# USBhub.net
KiCad netlist of a schematic drawn in Altium Designer
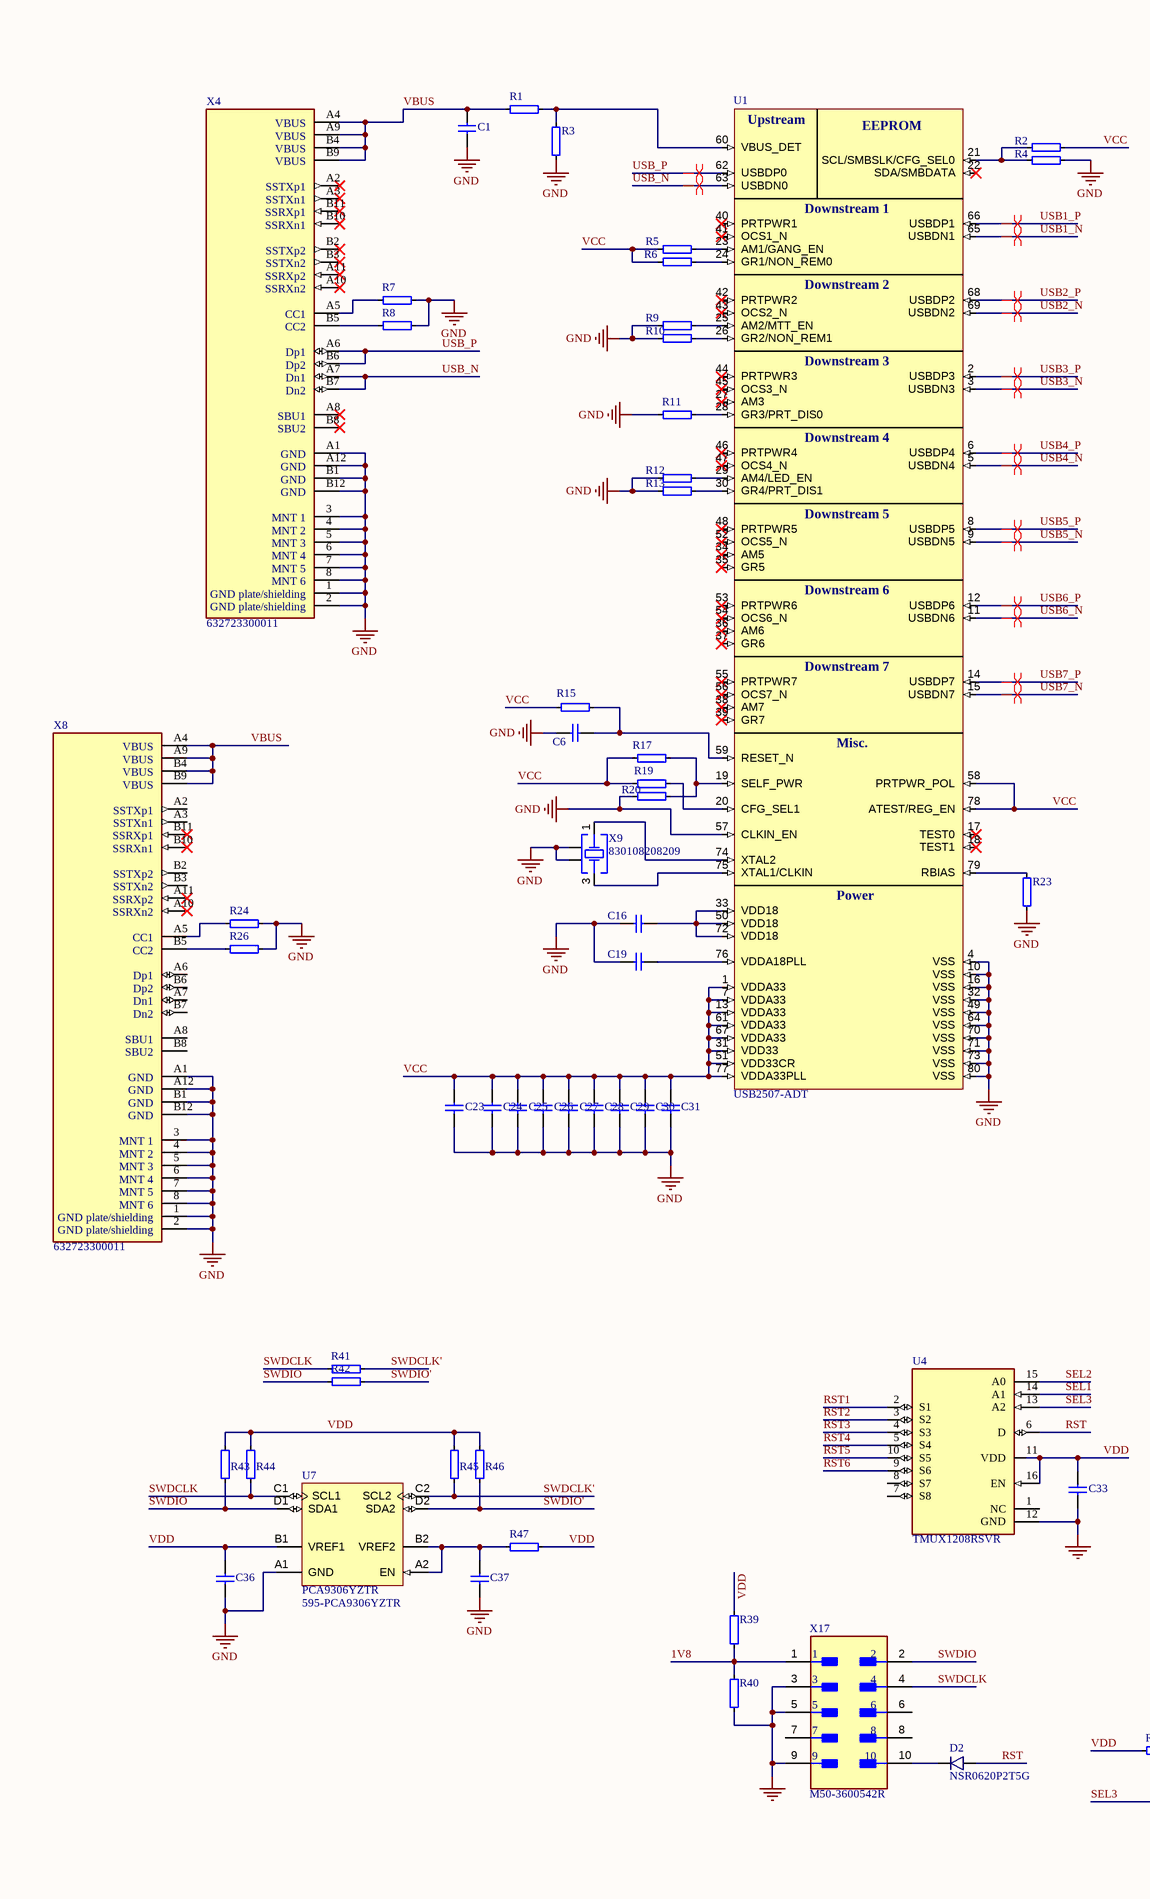
[diagram p0: USBhub.SchDoc, left]
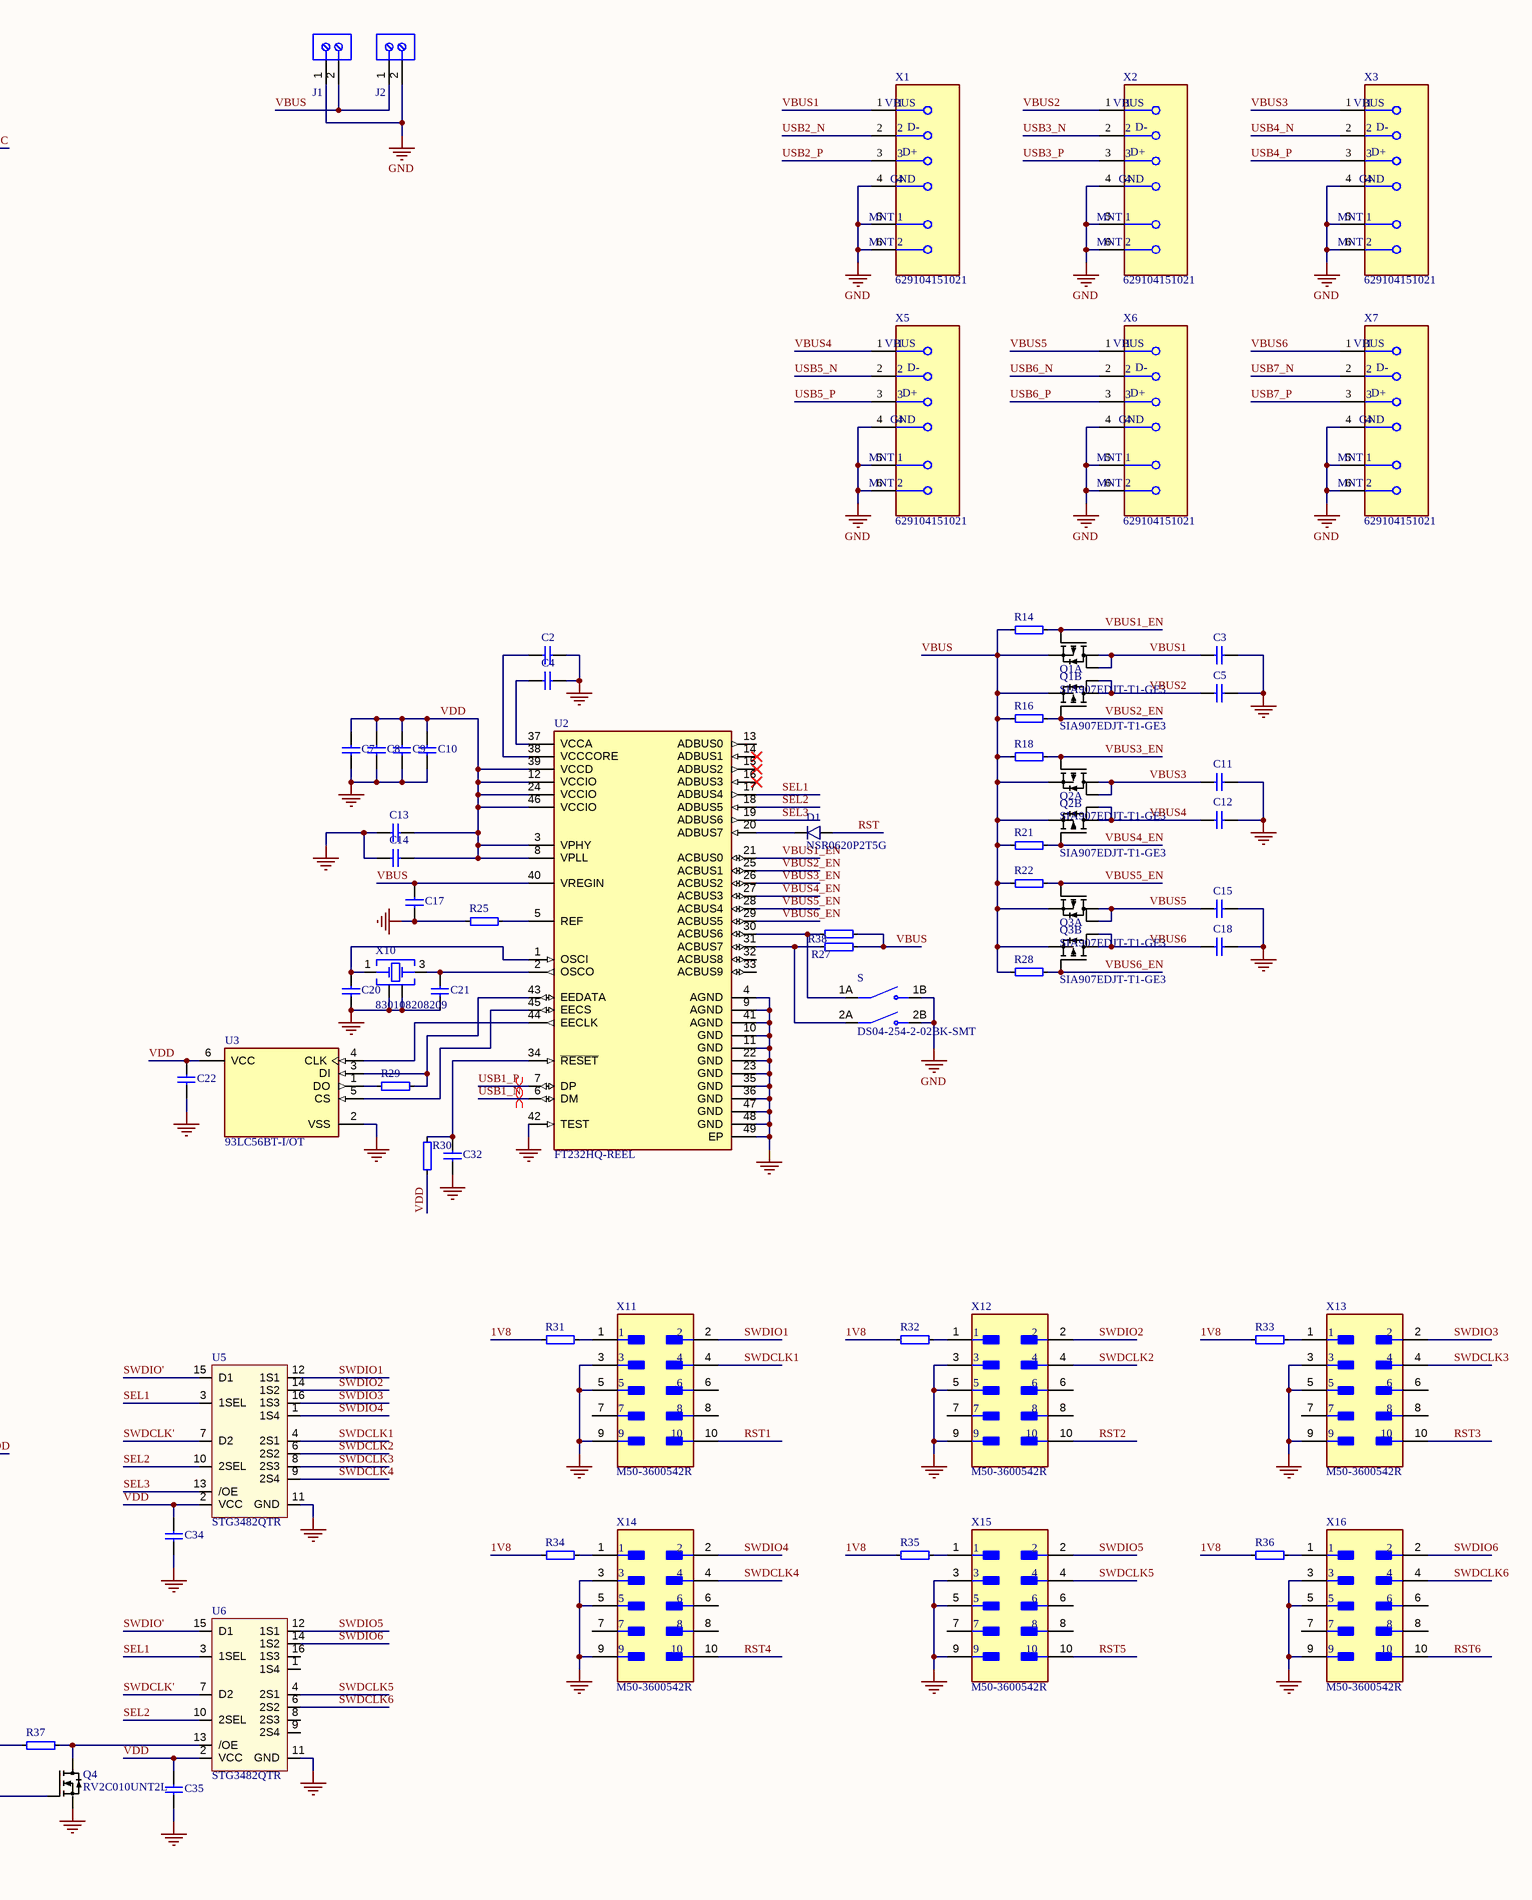
[diagram p1: USBhub.SchDoc, right]

(export (version "E")
  (design (tool "Eeschema 10.0.6"))
  (components
    (comp (ref "C1") (value "C0402") (footprint "CAPC1005X04L") (libsource (lib "Schlib1") (part "C0402")))
    (comp (ref "C2") (value "C0201") (footprint "CAPC0603X03L_C") (libsource (lib "Schlib1") (part "C0201")))
    (comp (ref "C3") (value "C0402") (footprint "CAPC1005X04L") (libsource (lib "Schlib1") (part "C0402")))
    (comp (ref "C4") (value "C0201") (footprint "CAPC0603X03L_C") (libsource (lib "Schlib1") (part "C0201")))
    (comp (ref "C5") (value "C0402") (footprint "CAPC1005X04L") (libsource (lib "Schlib1") (part "C0402")))
    (comp (ref "C6") (value "C0201") (footprint "CAPC0603X03L_C") (libsource (lib "Schlib1") (part "C0201")))
    (comp (ref "C7") (value "C0201") (footprint "CAPC0603X03L_C") (libsource (lib "Schlib1") (part "C0201")))
    (comp (ref "C8") (value "C0201") (footprint "CAPC0603X03L_C") (libsource (lib "Schlib1") (part "C0201")))
    (comp (ref "C9") (value "C0201") (footprint "CAPC0603X03L_C") (libsource (lib "Schlib1") (part "C0201")))
    (comp (ref "C10") (value "C0201") (footprint "CAPC0603X03L_C") (libsource (lib "Schlib1") (part "C0201")))
    (comp (ref "C11") (value "C0402") (footprint "CAPC1005X04L") (libsource (lib "Schlib1") (part "C0402")))
    (comp (ref "C12") (value "C0402") (footprint "CAPC1005X04L") (libsource (lib "Schlib1") (part "C0402")))
    (comp (ref "C13") (value "C0201") (footprint "CAPC0603X03L_C") (libsource (lib "Schlib1") (part "C0201")))
    (comp (ref "C14") (value "C0201") (footprint "CAPC0603X03L_C") (libsource (lib "Schlib1") (part "C0201")))
    (comp (ref "C15") (value "C0402") (footprint "CAPC1005X04L") (libsource (lib "Schlib1") (part "C0402")))
    (comp (ref "C16") (value "C0402") (footprint "CAPC1005X04L") (libsource (lib "Schlib1") (part "C0402")))
    (comp (ref "C17") (value "C0201") (footprint "CAPC0603X03L_C") (libsource (lib "Schlib1") (part "C0201")))
    (comp (ref "C18") (value "C0402") (footprint "CAPC1005X04L") (libsource (lib "Schlib1") (part "C0402")))
    (comp (ref "C19") (value "C0402") (footprint "CAPC1005X04L") (libsource (lib "Schlib1") (part "C0402")))
    (comp (ref "C20") (value "C0201") (footprint "CAPC0603X03L_C") (libsource (lib "Schlib1") (part "C0201")))
    (comp (ref "C21") (value "C0201") (footprint "CAPC0603X03L_C") (libsource (lib "Schlib1") (part "C0201")))
    (comp (ref "C22") (value "C0201") (footprint "CAPC0603X03L_C") (libsource (lib "Schlib1") (part "C0201")))
    (comp (ref "C23") (value "C0603") (footprint "CAPC1608X06L") (libsource (lib "Schlib1") (part "C0603")))
    (comp (ref "C24") (value "C0201") (footprint "CAPC0603X03L_C") (libsource (lib "Schlib1") (part "C0201")))
    (comp (ref "C25") (value "C0201") (footprint "CAPC0603X03L_C") (libsource (lib "Schlib1") (part "C0201")))
    (comp (ref "C26") (value "C0201") (footprint "CAPC0603X03L_C") (libsource (lib "Schlib1") (part "C0201")))
    (comp (ref "C27") (value "C0201") (footprint "CAPC0603X03L_C") (libsource (lib "Schlib1") (part "C0201")))
    (comp (ref "C28") (value "C0201") (footprint "CAPC0603X03L_C") (libsource (lib "Schlib1") (part "C0201")))
    (comp (ref "C29") (value "C0201") (footprint "CAPC0603X03L_C") (libsource (lib "Schlib1") (part "C0201")))
    (comp (ref "C30") (value "C0201") (footprint "CAPC0603X03L_C") (libsource (lib "Schlib1") (part "C0201")))
    (comp (ref "C31") (value "C0201") (footprint "CAPC0603X03L_C") (libsource (lib "Schlib1") (part "C0201")))
    (comp (ref "C32") (value "C0201") (footprint "CAPC0603X03L_C") (libsource (lib "Schlib1") (part "C0201")))
    (comp (ref "C33") (value "C0201") (footprint "CAPC0603X03L_C") (libsource (lib "Schlib1") (part "C0201")))
    (comp (ref "C34") (value "C0201") (footprint "CAPC0603X03L_C") (libsource (lib "Schlib1") (part "C0201")))
    (comp (ref "C35") (value "C0201") (footprint "CAPC0603X03L_C") (libsource (lib "Schlib1") (part "C0201")))
    (comp (ref "C36") (value "C0201") (footprint "CAPC0603X03L_C") (libsource (lib "Schlib1") (part "C0201")))
    (comp (ref "C37") (value "C0201") (footprint "CAPC0603X03L_C") (libsource (lib "Schlib1") (part "C0201")))
    (comp (ref "D1")
      (value "NSR0620P2T5G")
      (footprint "SODFL100X40-2N")
      (description "20V schottky barrier diode, Vf 350 mV @ 100 mA, Ir 2.0 µA @ 10 V, If 500 mA")
      (fields (field (name "MANUFACTURER") "ON Semiconductor"))
      (libsource (lib "Schlib1") (part "NSR0620P2T5G"))
    )
    (comp (ref "D2")
      (value "NSR0620P2T5G")
      (footprint "SODFL100X40-2N")
      (description "20V schottky barrier diode, Vf 350 mV @ 100 mA, Ir 2.0 µA @ 10 V, If 500 mA")
      (fields (field (name "MANUFACTURER") "ON Semiconductor"))
      (libsource (lib "Schlib1") (part "NSR0620P2T5G"))
    )
    (comp (ref "J1")
      (value "691103110002")
      (footprint "691103110002")
      (description "WR-TBL Series 1031 Horizontal Entry Modular, Through Hole, pitch 3.5mm, 2p")
      (fields (field (name "MANUFACTURER") "Wurth Elektronik"))
      (libsource (lib "Schlib1") (part "691103110002"))
    )
    (comp (ref "J2")
      (value "691103110002")
      (footprint "691103110002")
      (description "WR-TBL Series 1031 Horizontal Entry Modular, Through Hole, pitch 3.5mm, 2p")
      (fields (field (name "MANUFACTURER") "Wurth Elektronik"))
      (libsource (lib "Schlib1") (part "691103110002"))
    )
    (comp (ref "Q1")
      (value "SIA907EDJT-T1-GE3")
      (footprint "FP-C-07431-DUAL-MFG")
      (description "SiA907EDJT Series Dual P Channel 20 V 0.057 Ohm 7.8 W Mosfet - PowerPAK SC-70-6L")
      (fields (field (name "MANUFACTURER") "Vishay Siliconix"))
      (libsource (lib "Schlib1") (part "SIA907EDJT-T1-GE3"))
    )
    (comp (ref "Q2")
      (value "SIA907EDJT-T1-GE3")
      (footprint "FP-C-07431-DUAL-MFG")
      (description "SiA907EDJT Series Dual P Channel 20 V 0.057 Ohm 7.8 W Mosfet - PowerPAK SC-70-6L")
      (fields (field (name "MANUFACTURER") "Vishay Siliconix"))
      (libsource (lib "Schlib1") (part "SIA907EDJT-T1-GE3"))
    )
    (comp (ref "Q3")
      (value "SIA907EDJT-T1-GE3")
      (footprint "FP-C-07431-DUAL-MFG")
      (description "SiA907EDJT Series Dual P Channel 20 V 0.057 Ohm 7.8 W Mosfet - PowerPAK SC-70-6L")
      (fields (field (name "MANUFACTURER") "Vishay Siliconix"))
      (libsource (lib "Schlib1") (part "SIA907EDJT-T1-GE3"))
    )
    (comp (ref "Q4")
      (value "RV2C010UNT2L")
      (footprint "DFN65P100X40-3L")
      (description "MOSFET Transistor, N Channel, 1 A, 20 V, 0.34 ohm, 4.5 V, 1 V RoHS Compliant: Yes")
      (fields (field (name "MANUFACTURER") "Rohm"))
      (libsource (lib "Schlib1") (part "RV2C010UNT2L"))
    )
    (comp (ref "R1") (value "R0201") (footprint "RESC0603X03L_C") (libsource (lib "Schlib1") (part "R0201")))
    (comp (ref "R2") (value "R0201") (footprint "RESC0603X03L_C") (libsource (lib "Schlib1") (part "R0201")))
    (comp (ref "R3") (value "R0201") (footprint "RESC0603X03L_C") (libsource (lib "Schlib1") (part "R0201")))
    (comp (ref "R4") (value "R0201") (footprint "RESC0603X03L_C") (libsource (lib "Schlib1") (part "R0201")))
    (comp (ref "R5") (value "R0201") (footprint "RESC0603X03L_C") (libsource (lib "Schlib1") (part "R0201")))
    (comp (ref "R6") (value "R0201") (footprint "RESC0603X03L_C") (libsource (lib "Schlib1") (part "R0201")))
    (comp (ref "R7") (value "R0201") (footprint "RESC0603X03L_C") (libsource (lib "Schlib1") (part "R0201")))
    (comp (ref "R8") (value "R0201") (footprint "RESC0603X03L_C") (libsource (lib "Schlib1") (part "R0201")))
    (comp (ref "R9") (value "R0201") (footprint "RESC0603X03L_C") (libsource (lib "Schlib1") (part "R0201")))
    (comp (ref "R10") (value "R0201") (footprint "RESC0603X03L_C") (libsource (lib "Schlib1") (part "R0201")))
    (comp (ref "R11") (value "R0201") (footprint "RESC0603X03L_C") (libsource (lib "Schlib1") (part "R0201")))
    (comp (ref "R12") (value "R0201") (footprint "RESC0603X03L_C") (libsource (lib "Schlib1") (part "R0201")))
    (comp (ref "R13") (value "R0201") (footprint "RESC0603X03L_C") (libsource (lib "Schlib1") (part "R0201")))
    (comp (ref "R14") (value "R0201") (footprint "RESC0603X03L_C") (libsource (lib "Schlib1") (part "R0201")))
    (comp (ref "R15") (value "R0201") (footprint "RESC0603X03L_C") (libsource (lib "Schlib1") (part "R0201")))
    (comp (ref "R16") (value "R0201") (footprint "RESC0603X03L_C") (libsource (lib "Schlib1") (part "R0201")))
    (comp (ref "R17") (value "R0201") (footprint "RESC0603X03L_C") (libsource (lib "Schlib1") (part "R0201")))
    (comp (ref "R18") (value "R0201") (footprint "RESC0603X03L_C") (libsource (lib "Schlib1") (part "R0201")))
    (comp (ref "R19") (value "R0201") (footprint "RESC0603X03L_C") (libsource (lib "Schlib1") (part "R0201")))
    (comp (ref "R20") (value "R0201") (footprint "RESC0603X03L_C") (libsource (lib "Schlib1") (part "R0201")))
    (comp (ref "R21") (value "R0201") (footprint "RESC0603X03L_C") (libsource (lib "Schlib1") (part "R0201")))
    (comp (ref "R22") (value "R0201") (footprint "RESC0603X03L_C") (libsource (lib "Schlib1") (part "R0201")))
    (comp (ref "R23") (value "R0201") (footprint "RESC0603X03L_C") (libsource (lib "Schlib1") (part "R0201")))
    (comp (ref "R24") (value "R0201") (footprint "RESC0603X03L_C") (libsource (lib "Schlib1") (part "R0201")))
    (comp (ref "R25") (value "R0201") (footprint "RESC0603X03L_C") (libsource (lib "Schlib1") (part "R0201")))
    (comp (ref "R26") (value "R0201") (footprint "RESC0603X03L_C") (libsource (lib "Schlib1") (part "R0201")))
    (comp (ref "R27") (value "R0201") (footprint "RESC0603X03L_C") (libsource (lib "Schlib1") (part "R0201")))
    (comp (ref "R28") (value "R0201") (footprint "RESC0603X03L_C") (libsource (lib "Schlib1") (part "R0201")))
    (comp (ref "R29") (value "R0201") (footprint "RESC0603X03L_C") (libsource (lib "Schlib1") (part "R0201")))
    (comp (ref "R30") (value "R0201") (footprint "RESC0603X03L_C") (libsource (lib "Schlib1") (part "R0201")))
    (comp (ref "R31") (value "R0201") (footprint "RESC0603X03L_C") (libsource (lib "Schlib1") (part "R0201")))
    (comp (ref "R32") (value "R0201") (footprint "RESC0603X03L_C") (libsource (lib "Schlib1") (part "R0201")))
    (comp (ref "R33") (value "R0201") (footprint "RESC0603X03L_C") (libsource (lib "Schlib1") (part "R0201")))
    (comp (ref "R34") (value "R0201") (footprint "RESC0603X03L_C") (libsource (lib "Schlib1") (part "R0201")))
    (comp (ref "R35") (value "R0201") (footprint "RESC0603X03L_C") (libsource (lib "Schlib1") (part "R0201")))
    (comp (ref "R36") (value "R0201") (footprint "RESC0603X03L_C") (libsource (lib "Schlib1") (part "R0201")))
    (comp (ref "R37") (value "R0201") (footprint "RESC0603X03L_C") (libsource (lib "Schlib1") (part "R0201")))
    (comp (ref "R38") (value "R0201") (footprint "RESC0603X03L_C") (libsource (lib "Schlib1") (part "R0201")))
    (comp (ref "R39") (value "R0201") (footprint "RESC0603X03L_C") (libsource (lib "Schlib1") (part "R0201")))
    (comp (ref "R40") (value "R0201") (footprint "RESC0603X03L_C") (libsource (lib "Schlib1") (part "R0201")))
    (comp (ref "R41") (value "R0201") (footprint "RESC0603X03L_C") (libsource (lib "Schlib1") (part "R0201")))
    (comp (ref "R42") (value "R0201") (footprint "RESC0603X03L_C") (libsource (lib "Schlib1") (part "R0201")))
    (comp (ref "R43") (value "R0201") (footprint "RESC0603X03L_C") (libsource (lib "Schlib1") (part "R0201")))
    (comp (ref "R44") (value "R0201") (footprint "RESC0603X03L_C") (libsource (lib "Schlib1") (part "R0201")))
    (comp (ref "R45") (value "R0201") (footprint "RESC0603X03L_C") (libsource (lib "Schlib1") (part "R0201")))
    (comp (ref "R46") (value "R0201") (footprint "RESC0603X03L_C") (libsource (lib "Schlib1") (part "R0201")))
    (comp (ref "R47") (value "R0201") (footprint "RESC0603X03L_C") (libsource (lib "Schlib1") (part "R0201")))
    (comp (ref "S")
      (value "DS04-254-2-02BK-SMT")
      (footprint "PcbLib1:SW_DS04-254-2-02BK-SMT")
      (description "2 Pole, Flat Actuator, Flat Bottom, SMT Pin, DIP Switch")
      (fields (field (name "MF") "CUI Devices"))
      (libsource (lib "Schlib1") (part "DS04-254-2-02BK-SMT"))
    )
    (comp (ref "U1")
      (value "USB2507-ADT")
      (footprint "USB2507-ADT")
      (description "Low Speed/Full Speed/High Speed Compatible 7 Port Hub USB 2.0 1.8V/3.3V Tray 80-Pin TQFP")
      (fields (field (name "MANUFACTURER") "Microchip"))
      (libsource (lib "Schlib1") (part "USB2507-ADT"))
    )
    (comp (ref "U2")
      (value "FT232HQ-REEL")
      (footprint "FT232HQ")
      (description "Full Speed/High Speed USB Interface Device USB 2.0 3.3V T/R 48-Pin QFN EP")
      (fields (field (name "MANUFACTURER") "FTDI"))
      (libsource (lib "Schlib1") (part "FT232HQ-REEL"))
    )
    (comp (ref "U3")
      (value "93LC56BT-I/OT")
      (footprint "93LC56BT-I/OT_sot23-6")
      (description "RES 1 OHM 1/2W 5% AXIAL")
      (fields (field (name "MANUFACTURER") "Microchip"))
      (libsource (lib "Schlib1") (part "93LC56BT-I/OT"))
    )
    (comp (ref "U4")
      (value "TMUX1208RSVR")
      (footprint "FP-RSV0016A-MFG")
      (description "5-V, 8: 1, 1-channel general-purpose analog multiplexer with 1.8-V input logic 16-UQFN -40 to 125")
      (fields (field (name "MANUFACTURER") "Texas Instruments"))
      (libsource (lib "Schlib1") (part "TMUX1208RSVR"))
    )
    (comp (ref "U5")
      (value "STG3482QTR")
      (footprint "STG3482QTR")
      (description "Low Voltage Dual SP4T Switch with Break-Before-Make Feat.")
      (fields (field (name "MANUFACTURER") "STMicroelectronics"))
      (libsource (lib "Schlib1") (part "STG3482QTR"))
    )
    (comp (ref "U6")
      (value "STG3482QTR")
      (footprint "STG3482QTR")
      (description "Low Voltage Dual SP4T Switch with Break-Before-Make Feat.")
      (fields (field (name "MANUFACTURER") "STMicroelectronics"))
      (libsource (lib "Schlib1") (part "STG3482QTR"))
    )
    (comp (ref "U7")
      (value "PCA9306YZTR")
      (footprint "PCA9306YZTR")
      (description "PCA9306 2-BIT Bidirectional I2C")
      (fields
        (field (name "MANUFACTURER") "Texas Instruments")
        (field (name "SUPPLIER PART NUMBER 1") "595-PCA9306YZTR")
      )
      (libsource (lib "Schlib1") (part "PCA9306YZTR"))
    )
    (comp (ref "X1")
      (value "629104151021")
      (footprint "FP-629104151021-MFG")
      (description "USB 2.0 Type A Receptacle WR-COM, Horizontal, SMT, with Pegs")
      (fields (field (name "MANUFACTURER") "Wurth Electronics"))
      (libsource (lib "Schlib1") (part "629104151021"))
    )
    (comp (ref "X2")
      (value "629104151021")
      (footprint "FP-629104151021-MFG")
      (description "USB 2.0 Type A Receptacle WR-COM, Horizontal, SMT, with Pegs")
      (fields (field (name "MANUFACTURER") "Wurth Electronics"))
      (libsource (lib "Schlib1") (part "629104151021"))
    )
    (comp (ref "X3")
      (value "629104151021")
      (footprint "FP-629104151021-MFG")
      (description "USB 2.0 Type A Receptacle WR-COM, Horizontal, SMT, with Pegs")
      (fields (field (name "MANUFACTURER") "Wurth Electronics"))
      (libsource (lib "Schlib1") (part "629104151021"))
    )
    (comp (ref "X4")
      (value "632723300011")
      (footprint "FP-632723300011-MFG")
      (description "Conn USB 3.1 Type C RCP 24 POS 0.5mm/0.4mm Solder RA SMD/Thru-Hole 24 Terminal 1 Port T/R")
      (fields (field (name "MANUFACTURER") "Wurth Electronics"))
      (libsource (lib "Schlib1") (part "632723300011"))
    )
    (comp (ref "X5")
      (value "629104151021")
      (footprint "FP-629104151021-MFG")
      (description "USB 2.0 Type A Receptacle WR-COM, Horizontal, SMT, with Pegs")
      (fields (field (name "MANUFACTURER") "Wurth Electronics"))
      (libsource (lib "Schlib1") (part "629104151021"))
    )
    (comp (ref "X6")
      (value "629104151021")
      (footprint "FP-629104151021-MFG")
      (description "USB 2.0 Type A Receptacle WR-COM, Horizontal, SMT, with Pegs")
      (fields (field (name "MANUFACTURER") "Wurth Electronics"))
      (libsource (lib "Schlib1") (part "629104151021"))
    )
    (comp (ref "X7")
      (value "629104151021")
      (footprint "FP-629104151021-MFG")
      (description "USB 2.0 Type A Receptacle WR-COM, Horizontal, SMT, with Pegs")
      (fields (field (name "MANUFACTURER") "Wurth Electronics"))
      (libsource (lib "Schlib1") (part "629104151021"))
    )
    (comp (ref "X8")
      (value "632723300011")
      (footprint "FP-632723300011-MFG")
      (description "Conn USB 3.1 Type C RCP 24 POS 0.5mm/0.4mm Solder RA SMD/Thru-Hole 24 Terminal 1 Port T/R")
      (fields (field (name "MANUFACTURER") "Wurth Electronics"))
      (libsource (lib "Schlib1") (part "632723300011"))
    )
    (comp (ref "X9")
      (value "830108208209")
      (footprint "WE-XTAL_CFPX-218")
      (fields (field (name "MANUFACTURER") "Wurth Electronics"))
      (libsource (lib "Schlib1") (part "830108208209"))
    )
    (comp (ref "X10")
      (value "830108208209")
      (footprint "WE-XTAL_CFPX-218")
      (fields (field (name "MANUFACTURER") "Wurth Electronics"))
      (libsource (lib "Schlib1") (part "830108208209"))
    )
    (comp (ref "X11")
      (value "M50-3600542R")
      (footprint "M50-3600542R")
      (description "Conn Unshrouded Header M 10 POS 1.27mm Solder ST Top Entry SMD T/R")
      (fields (field (name "MANUFACTURER") "Harwin"))
      (libsource (lib "Schlib1") (part "M50-3600542R"))
    )
    (comp (ref "X12")
      (value "M50-3600542R")
      (footprint "M50-3600542R")
      (description "Conn Unshrouded Header M 10 POS 1.27mm Solder ST Top Entry SMD T/R")
      (fields (field (name "MANUFACTURER") "Harwin"))
      (libsource (lib "Schlib1") (part "M50-3600542R"))
    )
    (comp (ref "X13")
      (value "M50-3600542R")
      (footprint "M50-3600542R")
      (description "Conn Unshrouded Header M 10 POS 1.27mm Solder ST Top Entry SMD T/R")
      (fields (field (name "MANUFACTURER") "Harwin"))
      (libsource (lib "Schlib1") (part "M50-3600542R"))
    )
    (comp (ref "X14")
      (value "M50-3600542R")
      (footprint "M50-3600542R")
      (description "Conn Unshrouded Header M 10 POS 1.27mm Solder ST Top Entry SMD T/R")
      (fields (field (name "MANUFACTURER") "Harwin"))
      (libsource (lib "Schlib1") (part "M50-3600542R"))
    )
    (comp (ref "X15")
      (value "M50-3600542R")
      (footprint "M50-3600542R")
      (description "Conn Unshrouded Header M 10 POS 1.27mm Solder ST Top Entry SMD T/R")
      (fields (field (name "MANUFACTURER") "Harwin"))
      (libsource (lib "Schlib1") (part "M50-3600542R"))
    )
    (comp (ref "X16")
      (value "M50-3600542R")
      (footprint "M50-3600542R")
      (description "Conn Unshrouded Header M 10 POS 1.27mm Solder ST Top Entry SMD T/R")
      (fields (field (name "MANUFACTURER") "Harwin"))
      (libsource (lib "Schlib1") (part "M50-3600542R"))
    )
    (comp (ref "X17")
      (value "M50-3600542R")
      (footprint "M50-3600542R")
      (description "Conn Unshrouded Header M 10 POS 1.27mm Solder ST Top Entry SMD T/R")
      (fields (field (name "MANUFACTURER") "Harwin"))
      (libsource (lib "Schlib1") (part "M50-3600542R"))
    )
  )
  (nets
    (net (code "1") (name "/1V8") (class "Default")
      (node (ref "R31") (pin "2") (pinfunction "2_2") (pintype "passive"))
      (node (ref "R32") (pin "2") (pinfunction "2_2") (pintype "passive"))
      (node (ref "R33") (pin "2") (pinfunction "2_2") (pintype "passive"))
      (node (ref "R34") (pin "2") (pinfunction "2_2") (pintype "passive"))
      (node (ref "R35") (pin "2") (pinfunction "2_2") (pintype "passive"))
      (node (ref "R36") (pin "2") (pinfunction "2_2") (pintype "passive"))
      (node (ref "R39") (pin "2") (pinfunction "2_2") (pintype "passive"))
      (node (ref "R40") (pin "1") (pinfunction "1_1") (pintype "passive"))
      (node (ref "X17") (pin "1") (pinfunction "1_1") (pintype "passive"))
    )
    (net (code "2") (name "/RST") (class "Default")
      (node (ref "D1") (pin "2") (pinfunction "A_2") (pintype "passive"))
      (node (ref "D2") (pin "2") (pinfunction "A_2") (pintype "passive"))
      (node (ref "U4") (pin "6") (pinfunction "D_6") (pintype "bidirectional"))
    )
    (net (code "3") (name "/RST1") (class "Default")
      (node (ref "U4") (pin "2") (pinfunction "S1_2") (pintype "bidirectional"))
      (node (ref "X11") (pin "10") (pinfunction "10_10") (pintype "passive"))
    )
    (net (code "4") (name "/RST2") (class "Default")
      (node (ref "U4") (pin "3") (pinfunction "S2_3") (pintype "bidirectional"))
      (node (ref "X12") (pin "10") (pinfunction "10_10") (pintype "passive"))
    )
    (net (code "5") (name "/RST3") (class "Default")
      (node (ref "U4") (pin "4") (pinfunction "S3_4") (pintype "bidirectional"))
      (node (ref "X13") (pin "10") (pinfunction "10_10") (pintype "passive"))
    )
    (net (code "6") (name "/RST4") (class "Default")
      (node (ref "U4") (pin "5") (pinfunction "S4_5") (pintype "bidirectional"))
      (node (ref "X14") (pin "10") (pinfunction "10_10") (pintype "passive"))
    )
    (net (code "7") (name "/RST5") (class "Default")
      (node (ref "U4") (pin "10") (pinfunction "S5_10") (pintype "bidirectional"))
      (node (ref "X15") (pin "10") (pinfunction "10_10") (pintype "passive"))
    )
    (net (code "8") (name "/RST6") (class "Default")
      (node (ref "U4") (pin "9") (pinfunction "S6_9") (pintype "bidirectional"))
      (node (ref "X16") (pin "10") (pinfunction "10_10") (pintype "passive"))
    )
    (net (code "9") (name "/SEL1") (class "Default")
      (node (ref "U2") (pin "17") (pinfunction "ADBUS4_17") (pintype "output"))
      (node (ref "U4") (pin "14") (pinfunction "A1_14") (pintype "input"))
      (node (ref "U5") (pin "3") (pinfunction "1SEL_3") (pintype "passive"))
      (node (ref "U6") (pin "3") (pinfunction "1SEL_3") (pintype "passive"))
    )
    (net (code "10") (name "/SEL2") (class "Default")
      (node (ref "U2") (pin "18") (pinfunction "ADBUS5_18") (pintype "input"))
      (node (ref "U4") (pin "15") (pinfunction "A0_15") (pintype "passive"))
      (node (ref "U5") (pin "10") (pinfunction "2SEL_10") (pintype "passive"))
      (node (ref "U6") (pin "10") (pinfunction "2SEL_10") (pintype "passive"))
    )
    (net (code "11") (name "/SEL3") (class "Default")
      (node (ref "Q4") (pin "1") (pinfunction "G_1") (pintype "passive"))
      (node (ref "U2") (pin "19") (pinfunction "ADBUS6_19") (pintype "output"))
      (node (ref "U4") (pin "13") (pinfunction "A2_13") (pintype "input"))
      (node (ref "U5") (pin "13") (pinfunction "/OE_13") (pintype "passive"))
    )
    (net (code "12") (name "/SWDCLK") (class "Default")
      (node (ref "R41") (pin "2") (pinfunction "2_2") (pintype "passive"))
      (node (ref "R44") (pin "1") (pinfunction "1_1") (pintype "passive"))
      (node (ref "U7") (pin "C1") (pinfunction "SCL1_C1") (pintype "bidirectional"))
      (node (ref "X17") (pin "4") (pinfunction "4_4") (pintype "passive"))
    )
    (net (code "13") (name "/SWDCLK'") (class "Default")
      (node (ref "R41") (pin "1") (pinfunction "1_1") (pintype "passive"))
      (node (ref "R45") (pin "1") (pinfunction "1_1") (pintype "passive"))
      (node (ref "U5") (pin "7") (pinfunction "D2_7") (pintype "passive"))
      (node (ref "U6") (pin "7") (pinfunction "D2_7") (pintype "passive"))
      (node (ref "U7") (pin "C2") (pinfunction "SCL2_C2") (pintype "bidirectional"))
    )
    (net (code "14") (name "/SWDCLK1") (class "Default")
      (node (ref "U5") (pin "4") (pinfunction "2S1_4") (pintype "passive"))
      (node (ref "X11") (pin "4") (pinfunction "4_4") (pintype "passive"))
    )
    (net (code "15") (name "/SWDCLK2") (class "Default")
      (node (ref "U5") (pin "6") (pinfunction "2S2_6") (pintype "passive"))
      (node (ref "X12") (pin "4") (pinfunction "4_4") (pintype "passive"))
    )
    (net (code "16") (name "/SWDCLK3") (class "Default")
      (node (ref "U5") (pin "8") (pinfunction "2S3_8") (pintype "passive"))
      (node (ref "X13") (pin "4") (pinfunction "4_4") (pintype "passive"))
    )
    (net (code "17") (name "/SWDCLK4") (class "Default")
      (node (ref "U5") (pin "9") (pinfunction "2S4_9") (pintype "passive"))
      (node (ref "X14") (pin "4") (pinfunction "4_4") (pintype "passive"))
    )
    (net (code "18") (name "/SWDCLK5") (class "Default")
      (node (ref "U6") (pin "4") (pinfunction "2S1_4") (pintype "passive"))
      (node (ref "X15") (pin "4") (pinfunction "4_4") (pintype "passive"))
    )
    (net (code "19") (name "/SWDCLK6") (class "Default")
      (node (ref "U6") (pin "6") (pinfunction "2S2_6") (pintype "passive"))
      (node (ref "X16") (pin "4") (pinfunction "4_4") (pintype "passive"))
    )
    (net (code "20") (name "/SWDIO") (class "Default")
      (node (ref "R42") (pin "2") (pinfunction "2_2") (pintype "passive"))
      (node (ref "R43") (pin "1") (pinfunction "1_1") (pintype "passive"))
      (node (ref "U7") (pin "D1") (pinfunction "SDA1_D1") (pintype "bidirectional"))
      (node (ref "X17") (pin "2") (pinfunction "2_2") (pintype "passive"))
    )
    (net (code "21") (name "/SWDIO'") (class "Default")
      (node (ref "R42") (pin "1") (pinfunction "1_1") (pintype "passive"))
      (node (ref "R46") (pin "1") (pinfunction "1_1") (pintype "passive"))
      (node (ref "U5") (pin "15") (pinfunction "D1_15") (pintype "passive"))
      (node (ref "U6") (pin "15") (pinfunction "D1_15") (pintype "passive"))
      (node (ref "U7") (pin "D2") (pinfunction "SDA2_D2") (pintype "bidirectional"))
    )
    (net (code "22") (name "/SWDIO1") (class "Default")
      (node (ref "U5") (pin "12") (pinfunction "1S1_12") (pintype "passive"))
      (node (ref "X11") (pin "2") (pinfunction "2_2") (pintype "passive"))
    )
    (net (code "23") (name "/SWDIO2") (class "Default")
      (node (ref "U5") (pin "14") (pinfunction "1S2_14") (pintype "passive"))
      (node (ref "X12") (pin "2") (pinfunction "2_2") (pintype "passive"))
    )
    (net (code "24") (name "/SWDIO3") (class "Default")
      (node (ref "U5") (pin "16") (pinfunction "1S3_16") (pintype "passive"))
      (node (ref "X13") (pin "2") (pinfunction "2_2") (pintype "passive"))
    )
    (net (code "25") (name "/SWDIO4") (class "Default")
      (node (ref "U5") (pin "1") (pinfunction "1S4_1") (pintype "passive"))
      (node (ref "X14") (pin "2") (pinfunction "2_2") (pintype "passive"))
    )
    (net (code "26") (name "/SWDIO5") (class "Default")
      (node (ref "U6") (pin "12") (pinfunction "1S1_12") (pintype "passive"))
      (node (ref "X15") (pin "2") (pinfunction "2_2") (pintype "passive"))
    )
    (net (code "27") (name "/SWDIO6") (class "Default")
      (node (ref "U6") (pin "14") (pinfunction "1S2_14") (pintype "passive"))
      (node (ref "X16") (pin "2") (pinfunction "2_2") (pintype "passive"))
    )
    (net (code "28") (name "/USB1_N") (class "Default")
      (node (ref "U1") (pin "65") (pinfunction "USBDN1_65") (pintype "input"))
      (node (ref "U2") (pin "6") (pinfunction "DM_6") (pintype "bidirectional"))
    )
    (net (code "29") (name "/USB1_P") (class "Default")
      (node (ref "U1") (pin "66") (pinfunction "USBDP1_66") (pintype "input"))
      (node (ref "U2") (pin "7") (pinfunction "DP_7") (pintype "bidirectional"))
    )
    (net (code "30") (name "/USB2_N") (class "Default")
      (node (ref "U1") (pin "69") (pinfunction "USBDN2_69") (pintype "input"))
      (node (ref "X1") (pin "2") (pinfunction "2_2") (pintype "passive"))
    )
    (net (code "31") (name "/USB2_P") (class "Default")
      (node (ref "U1") (pin "68") (pinfunction "USBDP2_68") (pintype "input"))
      (node (ref "X1") (pin "3") (pinfunction "3_3") (pintype "passive"))
    )
    (net (code "32") (name "/USB3_N") (class "Default")
      (node (ref "U1") (pin "3") (pinfunction "USBDN3_3") (pintype "input"))
      (node (ref "X2") (pin "2") (pinfunction "2_2") (pintype "passive"))
    )
    (net (code "33") (name "/USB3_P") (class "Default")
      (node (ref "U1") (pin "2") (pinfunction "USBDP3_2") (pintype "input"))
      (node (ref "X2") (pin "3") (pinfunction "3_3") (pintype "passive"))
    )
    (net (code "34") (name "/USB4_N") (class "Default")
      (node (ref "U1") (pin "5") (pinfunction "USBDN4_5") (pintype "input"))
      (node (ref "X3") (pin "2") (pinfunction "2_2") (pintype "passive"))
    )
    (net (code "35") (name "/USB4_P") (class "Default")
      (node (ref "U1") (pin "6") (pinfunction "USBDP4_6") (pintype "input"))
      (node (ref "X3") (pin "3") (pinfunction "3_3") (pintype "passive"))
    )
    (net (code "36") (name "/USB5_N") (class "Default")
      (node (ref "U1") (pin "9") (pinfunction "USBDN5_9") (pintype "input"))
      (node (ref "X5") (pin "2") (pinfunction "2_2") (pintype "passive"))
    )
    (net (code "37") (name "/USB5_P") (class "Default")
      (node (ref "U1") (pin "8") (pinfunction "USBDP5_8") (pintype "input"))
      (node (ref "X5") (pin "3") (pinfunction "3_3") (pintype "passive"))
    )
    (net (code "38") (name "/USB6_N") (class "Default")
      (node (ref "U1") (pin "11") (pinfunction "USBDN6_11") (pintype "input"))
      (node (ref "X6") (pin "2") (pinfunction "2_2") (pintype "passive"))
    )
    (net (code "39") (name "/USB6_P") (class "Default")
      (node (ref "U1") (pin "12") (pinfunction "USBDP6_12") (pintype "input"))
      (node (ref "X6") (pin "3") (pinfunction "3_3") (pintype "passive"))
    )
    (net (code "40") (name "/USB7_N") (class "Default")
      (node (ref "U1") (pin "15") (pinfunction "USBDN7_15") (pintype "input"))
      (node (ref "X7") (pin "2") (pinfunction "2_2") (pintype "passive"))
    )
    (net (code "41") (name "/USB7_P") (class "Default")
      (node (ref "U1") (pin "14") (pinfunction "USBDP7_14") (pintype "input"))
      (node (ref "X7") (pin "3") (pinfunction "3_3") (pintype "passive"))
    )
    (net (code "42") (name "/USB_N") (class "Default")
      (node (ref "U1") (pin "63") (pinfunction "USBDN0_63") (pintype "input"))
      (node (ref "X4") (pin "A7") (pinfunction "Dn1_A7") (pintype "bidirectional"))
      (node (ref "X4") (pin "B7") (pinfunction "Dn2_B7") (pintype "bidirectional"))
    )
    (net (code "43") (name "/USB_P") (class "Default")
      (node (ref "U1") (pin "62") (pinfunction "USBDP0_62") (pintype "input"))
      (node (ref "X4") (pin "A6") (pinfunction "Dp1_A6") (pintype "bidirectional"))
      (node (ref "X4") (pin "B6") (pinfunction "Dp2_B6") (pintype "bidirectional"))
    )
    (net (code "44") (name "/VBUS") (class "Default")
      (node (ref "C1") (pin "2") (pinfunction "2_2") (pintype "passive"))
      (node (ref "C17") (pin "2") (pinfunction "2_2") (pintype "passive"))
      (node (ref "J1") (pin "2") (pinfunction "2_2") (pintype "passive"))
      (node (ref "J2") (pin "1") (pinfunction "1_1") (pintype "passive"))
      (node (ref "Q1") (pin "1") (pinfunction "S1_1") (pintype "passive"))
      (node (ref "Q1") (pin "4") (pinfunction "S2_4") (pintype "passive"))
      (node (ref "Q2") (pin "1") (pinfunction "S1_1") (pintype "passive"))
      (node (ref "Q2") (pin "4") (pinfunction "S2_4") (pintype "passive"))
      (node (ref "Q3") (pin "1") (pinfunction "S1_1") (pintype "passive"))
      (node (ref "Q3") (pin "4") (pinfunction "S2_4") (pintype "passive"))
      (node (ref "R1") (pin "2") (pinfunction "2_2") (pintype "passive"))
      (node (ref "R14") (pin "2") (pinfunction "2_2") (pintype "passive"))
      (node (ref "R16") (pin "2") (pinfunction "2_2") (pintype "passive"))
      (node (ref "R18") (pin "2") (pinfunction "2_2") (pintype "passive"))
      (node (ref "R21") (pin "2") (pinfunction "2_2") (pintype "passive"))
      (node (ref "R22") (pin "2") (pinfunction "2_2") (pintype "passive"))
      (node (ref "R27") (pin "2") (pinfunction "2_2") (pintype "passive"))
      (node (ref "R28") (pin "2") (pinfunction "2_2") (pintype "passive"))
      (node (ref "R38") (pin "2") (pinfunction "2_2") (pintype "passive"))
      (node (ref "U2") (pin "40") (pinfunction "VREGIN_40") (pintype "power_in"))
      (node (ref "X4") (pin "A4") (pinfunction "VBUS_A4") (pintype "power_in"))
      (node (ref "X4") (pin "A9") (pinfunction "VBUS_A9") (pintype "power_in"))
      (node (ref "X4") (pin "B4") (pinfunction "VBUS_B4") (pintype "power_in"))
      (node (ref "X4") (pin "B9") (pinfunction "VBUS_B9") (pintype "power_in"))
      (node (ref "X8") (pin "A4") (pinfunction "VBUS_A4") (pintype "power_in"))
      (node (ref "X8") (pin "A9") (pinfunction "VBUS_A9") (pintype "power_in"))
      (node (ref "X8") (pin "B4") (pinfunction "VBUS_B4") (pintype "power_in"))
      (node (ref "X8") (pin "B9") (pinfunction "VBUS_B9") (pintype "power_in"))
    )
    (net (code "45") (name "/VBUS1") (class "Default")
      (node (ref "C3") (pin "2") (pinfunction "2_2") (pintype "passive"))
      (node (ref "Q1") (pin "3") (pinfunction "D2_3") (pintype "passive"))
      (node (ref "Q1") (pin "8") (pinfunction "D2_8") (pintype "passive"))
      (node (ref "X1") (pin "1") (pinfunction "1_1") (pintype "passive"))
    )
    (net (code "46") (name "/VBUS1_EN") (class "Default")
      (node (ref "Q1") (pin "5") (pinfunction "G2_5") (pintype "passive"))
      (node (ref "R14") (pin "1") (pinfunction "1_1") (pintype "passive"))
      (node (ref "U2") (pin "21") (pinfunction "ACBUS0_21") (pintype "bidirectional"))
    )
    (net (code "47") (name "/VBUS2") (class "Default")
      (node (ref "C5") (pin "2") (pinfunction "2_2") (pintype "passive"))
      (node (ref "Q1") (pin "6") (pinfunction "D1_6") (pintype "passive"))
      (node (ref "Q1") (pin "7") (pinfunction "D1_7") (pintype "passive"))
      (node (ref "X2") (pin "1") (pinfunction "1_1") (pintype "passive"))
    )
    (net (code "48") (name "/VBUS2_EN") (class "Default")
      (node (ref "Q1") (pin "2") (pinfunction "G1_2") (pintype "passive"))
      (node (ref "R16") (pin "1") (pinfunction "1_1") (pintype "passive"))
      (node (ref "U2") (pin "25") (pinfunction "ACBUS1_25") (pintype "bidirectional"))
    )
    (net (code "49") (name "/VBUS3") (class "Default")
      (node (ref "C11") (pin "2") (pinfunction "2_2") (pintype "passive"))
      (node (ref "Q2") (pin "3") (pinfunction "D2_3") (pintype "passive"))
      (node (ref "Q2") (pin "8") (pinfunction "D2_8") (pintype "passive"))
      (node (ref "X3") (pin "1") (pinfunction "1_1") (pintype "passive"))
    )
    (net (code "50") (name "/VBUS3_EN") (class "Default")
      (node (ref "Q2") (pin "5") (pinfunction "G2_5") (pintype "passive"))
      (node (ref "R18") (pin "1") (pinfunction "1_1") (pintype "passive"))
      (node (ref "U2") (pin "26") (pinfunction "ACBUS2_26") (pintype "bidirectional"))
    )
    (net (code "51") (name "/VBUS4") (class "Default")
      (node (ref "C12") (pin "2") (pinfunction "2_2") (pintype "passive"))
      (node (ref "Q2") (pin "6") (pinfunction "D1_6") (pintype "passive"))
      (node (ref "Q2") (pin "7") (pinfunction "D1_7") (pintype "passive"))
      (node (ref "X5") (pin "1") (pinfunction "1_1") (pintype "passive"))
    )
    (net (code "52") (name "/VBUS4_EN") (class "Default")
      (node (ref "Q2") (pin "2") (pinfunction "G1_2") (pintype "passive"))
      (node (ref "R21") (pin "1") (pinfunction "1_1") (pintype "passive"))
      (node (ref "U2") (pin "27") (pinfunction "ACBUS3_27") (pintype "bidirectional"))
    )
    (net (code "53") (name "/VBUS5") (class "Default")
      (node (ref "C15") (pin "2") (pinfunction "2_2") (pintype "passive"))
      (node (ref "Q3") (pin "3") (pinfunction "D2_3") (pintype "passive"))
      (node (ref "Q3") (pin "8") (pinfunction "D2_8") (pintype "passive"))
      (node (ref "X6") (pin "1") (pinfunction "1_1") (pintype "passive"))
    )
    (net (code "54") (name "/VBUS5_EN") (class "Default")
      (node (ref "Q3") (pin "5") (pinfunction "G2_5") (pintype "passive"))
      (node (ref "R22") (pin "1") (pinfunction "1_1") (pintype "passive"))
      (node (ref "U2") (pin "28") (pinfunction "ACBUS4_28") (pintype "bidirectional"))
    )
    (net (code "55") (name "/VBUS6") (class "Default")
      (node (ref "C18") (pin "2") (pinfunction "2_2") (pintype "passive"))
      (node (ref "Q3") (pin "6") (pinfunction "D1_6") (pintype "passive"))
      (node (ref "Q3") (pin "7") (pinfunction "D1_7") (pintype "passive"))
      (node (ref "X7") (pin "1") (pinfunction "1_1") (pintype "passive"))
    )
    (net (code "56") (name "/VBUS6_EN") (class "Default")
      (node (ref "Q3") (pin "2") (pinfunction "G1_2") (pintype "passive"))
      (node (ref "R28") (pin "1") (pinfunction "1_1") (pintype "passive"))
      (node (ref "U2") (pin "29") (pinfunction "ACBUS5_29") (pintype "bidirectional"))
    )
    (net (code "57") (name "/VCC") (class "Default")
      (node (ref "C23") (pin "2") (pinfunction "2_2") (pintype "passive"))
      (node (ref "C24") (pin "2") (pinfunction "2_2") (pintype "passive"))
      (node (ref "C25") (pin "2") (pinfunction "2_2") (pintype "passive"))
      (node (ref "C26") (pin "2") (pinfunction "2_2") (pintype "passive"))
      (node (ref "C27") (pin "2") (pinfunction "2_2") (pintype "passive"))
      (node (ref "C28") (pin "2") (pinfunction "2_2") (pintype "passive"))
      (node (ref "C29") (pin "2") (pinfunction "2_2") (pintype "passive"))
      (node (ref "C30") (pin "2") (pinfunction "2_2") (pintype "passive"))
      (node (ref "C31") (pin "2") (pinfunction "2_2") (pintype "passive"))
      (node (ref "R15") (pin "1") (pinfunction "1_1") (pintype "passive"))
      (node (ref "R17") (pin "1") (pinfunction "1_1") (pintype "passive"))
      (node (ref "R19") (pin "1") (pinfunction "1_1") (pintype "passive"))
      (node (ref "R2") (pin "2") (pinfunction "2_2") (pintype "passive"))
      (node (ref "R5") (pin "1") (pinfunction "1_1") (pintype "passive"))
      (node (ref "R6") (pin "1") (pinfunction "1_1") (pintype "passive"))
      (node (ref "U1") (pin "1") (pinfunction "VDDA33_1") (pintype "input"))
      (node (ref "U1") (pin "13") (pinfunction "VDDA33_13") (pintype "input"))
      (node (ref "U1") (pin "31") (pinfunction "VDD33_31") (pintype "input"))
      (node (ref "U1") (pin "51") (pinfunction "VDD33CR_51") (pintype "input"))
      (node (ref "U1") (pin "58") (pinfunction "PRTPWR_POL_58") (pintype "input"))
      (node (ref "U1") (pin "61") (pinfunction "VDDA33_61") (pintype "input"))
      (node (ref "U1") (pin "67") (pinfunction "VDDA33_67") (pintype "input"))
      (node (ref "U1") (pin "7") (pinfunction "VDDA33_7") (pintype "input"))
      (node (ref "U1") (pin "77") (pinfunction "VDDA33PLL_77") (pintype "input"))
      (node (ref "U1") (pin "78") (pinfunction "ATEST/REG_EN_78") (pintype "input"))
    )
    (net (code "58") (name "/VDD") (class "Default")
      (node (ref "C10") (pin "2") (pinfunction "2_2") (pintype "passive"))
      (node (ref "C13") (pin "1") (pinfunction "1_1") (pintype "passive"))
      (node (ref "C14") (pin "1") (pinfunction "1_1") (pintype "passive"))
      (node (ref "C22") (pin "2") (pinfunction "2_2") (pintype "passive"))
      (node (ref "C33") (pin "2") (pinfunction "2_2") (pintype "passive"))
      (node (ref "C34") (pin "2") (pinfunction "2_2") (pintype "passive"))
      (node (ref "C35") (pin "2") (pinfunction "2_2") (pintype "passive"))
      (node (ref "C36") (pin "2") (pinfunction "2_2") (pintype "passive"))
      (node (ref "C7") (pin "2") (pinfunction "2_2") (pintype "passive"))
      (node (ref "C8") (pin "2") (pinfunction "2_2") (pintype "passive"))
      (node (ref "C9") (pin "2") (pinfunction "2_2") (pintype "passive"))
      (node (ref "R30") (pin "1") (pinfunction "1_1") (pintype "passive"))
      (node (ref "R37") (pin "2") (pinfunction "2_2") (pintype "passive"))
      (node (ref "R39") (pin "1") (pinfunction "1_1") (pintype "passive"))
      (node (ref "R43") (pin "2") (pinfunction "2_2") (pintype "passive"))
      (node (ref "R44") (pin "2") (pinfunction "2_2") (pintype "passive"))
      (node (ref "R45") (pin "2") (pinfunction "2_2") (pintype "passive"))
      (node (ref "R46") (pin "2") (pinfunction "2_2") (pintype "passive"))
      (node (ref "R47") (pin "1") (pinfunction "1_1") (pintype "passive"))
      (node (ref "U2") (pin "12") (pinfunction "VCCIO_12") (pintype "power_in"))
      (node (ref "U2") (pin "24") (pinfunction "VCCIO_24") (pintype "power_in"))
      (node (ref "U2") (pin "3") (pinfunction "VPHY_3") (pintype "power_in"))
      (node (ref "U2") (pin "39") (pinfunction "VCCD_39") (pintype "power_in"))
      (node (ref "U2") (pin "46") (pinfunction "VCCIO_46") (pintype "power_in"))
      (node (ref "U2") (pin "8") (pinfunction "VPLL_8") (pintype "power_in"))
      (node (ref "U3") (pin "6") (pinfunction "VCC_6") (pintype "power_in"))
      (node (ref "U4") (pin "11") (pinfunction "VDD_11") (pintype "power_in"))
      (node (ref "U4") (pin "16") (pinfunction "EN_16") (pintype "input"))
      (node (ref "U5") (pin "2") (pinfunction "VCC_2") (pintype "passive"))
      (node (ref "U6") (pin "2") (pinfunction "VCC_2") (pintype "passive"))
      (node (ref "U7") (pin "B1") (pinfunction "VREF1_B1") (pintype "power_in"))
    )
    (net (code "59") (name "GND") (class "Default")
      (node (ref "C1") (pin "1") (pinfunction "1_1") (pintype "passive"))
      (node (ref "C10") (pin "1") (pinfunction "1_1") (pintype "passive"))
      (node (ref "C11") (pin "1") (pinfunction "1_1") (pintype "passive"))
      (node (ref "C12") (pin "1") (pinfunction "1_1") (pintype "passive"))
      (node (ref "C13") (pin "2") (pinfunction "2_2") (pintype "passive"))
      (node (ref "C14") (pin "2") (pinfunction "2_2") (pintype "passive"))
      (node (ref "C15") (pin "1") (pinfunction "1_1") (pintype "passive"))
      (node (ref "C16") (pin "1") (pinfunction "1_1") (pintype "passive"))
      (node (ref "C17") (pin "1") (pinfunction "1_1") (pintype "passive"))
      (node (ref "C18") (pin "1") (pinfunction "1_1") (pintype "passive"))
      (node (ref "C19") (pin "1") (pinfunction "1_1") (pintype "passive"))
      (node (ref "C2") (pin "1") (pinfunction "1_1") (pintype "passive"))
      (node (ref "C20") (pin "2") (pinfunction "2_2") (pintype "passive"))
      (node (ref "C21") (pin "2") (pinfunction "2_2") (pintype "passive"))
      (node (ref "C22") (pin "1") (pinfunction "1_1") (pintype "passive"))
      (node (ref "C23") (pin "1") (pinfunction "1_1") (pintype "passive"))
      (node (ref "C24") (pin "1") (pinfunction "1_1") (pintype "passive"))
      (node (ref "C25") (pin "1") (pinfunction "1_1") (pintype "passive"))
      (node (ref "C26") (pin "1") (pinfunction "1_1") (pintype "passive"))
      (node (ref "C27") (pin "1") (pinfunction "1_1") (pintype "passive"))
      (node (ref "C28") (pin "1") (pinfunction "1_1") (pintype "passive"))
      (node (ref "C29") (pin "1") (pinfunction "1_1") (pintype "passive"))
      (node (ref "C3") (pin "1") (pinfunction "1_1") (pintype "passive"))
      (node (ref "C30") (pin "1") (pinfunction "1_1") (pintype "passive"))
      (node (ref "C31") (pin "1") (pinfunction "1_1") (pintype "passive"))
      (node (ref "C32") (pin "1") (pinfunction "1_1") (pintype "passive"))
      (node (ref "C33") (pin "1") (pinfunction "1_1") (pintype "passive"))
      (node (ref "C34") (pin "1") (pinfunction "1_1") (pintype "passive"))
      (node (ref "C35") (pin "1") (pinfunction "1_1") (pintype "passive"))
      (node (ref "C36") (pin "1") (pinfunction "1_1") (pintype "passive"))
      (node (ref "C37") (pin "1") (pinfunction "1_1") (pintype "passive"))
      (node (ref "C4") (pin "1") (pinfunction "1_1") (pintype "passive"))
      (node (ref "C5") (pin "1") (pinfunction "1_1") (pintype "passive"))
      (node (ref "C6") (pin "1") (pinfunction "1_1") (pintype "passive"))
      (node (ref "C7") (pin "1") (pinfunction "1_1") (pintype "passive"))
      (node (ref "C8") (pin "1") (pinfunction "1_1") (pintype "passive"))
      (node (ref "C9") (pin "1") (pinfunction "1_1") (pintype "passive"))
      (node (ref "J1") (pin "1") (pinfunction "1_1") (pintype "passive"))
      (node (ref "J2") (pin "2") (pinfunction "2_2") (pintype "passive"))
      (node (ref "Q4") (pin "2") (pinfunction "S_2") (pintype "passive"))
      (node (ref "R10") (pin "1") (pinfunction "1_1") (pintype "passive"))
      (node (ref "R11") (pin "1") (pinfunction "1_1") (pintype "passive"))
      (node (ref "R12") (pin "1") (pinfunction "1_1") (pintype "passive"))
      (node (ref "R13") (pin "1") (pinfunction "1_1") (pintype "passive"))
      (node (ref "R20") (pin "1") (pinfunction "1_1") (pintype "passive"))
      (node (ref "R23") (pin "2") (pinfunction "2_2") (pintype "passive"))
      (node (ref "R24") (pin "1") (pinfunction "1_1") (pintype "passive"))
      (node (ref "R25") (pin "1") (pinfunction "1_1") (pintype "passive"))
      (node (ref "R26") (pin "1") (pinfunction "1_1") (pintype "passive"))
      (node (ref "R3") (pin "2") (pinfunction "2_2") (pintype "passive"))
      (node (ref "R4") (pin "2") (pinfunction "2_2") (pintype "passive"))
      (node (ref "R40") (pin "2") (pinfunction "2_2") (pintype "passive"))
      (node (ref "R7") (pin "1") (pinfunction "1_1") (pintype "passive"))
      (node (ref "R8") (pin "1") (pinfunction "1_1") (pintype "passive"))
      (node (ref "R9") (pin "1") (pinfunction "1_1") (pintype "passive"))
      (node (ref "S") (pin "1B") (pinfunction "NO1_1B") (pintype "passive"))
      (node (ref "S") (pin "2B") (pinfunction "NO2_2B") (pintype "passive"))
      (node (ref "U1") (pin "10") (pinfunction "VSS_10") (pintype "input"))
      (node (ref "U1") (pin "16") (pinfunction "VSS_16") (pintype "input"))
      (node (ref "U1") (pin "32") (pinfunction "VSS_32") (pintype "input"))
      (node (ref "U1") (pin "4") (pinfunction "VSS_4") (pintype "input"))
      (node (ref "U1") (pin "49") (pinfunction "VSS_49") (pintype "input"))
      (node (ref "U1") (pin "57") (pinfunction "CLKIN_EN_57") (pintype "input"))
      (node (ref "U1") (pin "64") (pinfunction "VSS_64") (pintype "input"))
      (node (ref "U1") (pin "70") (pinfunction "VSS_70") (pintype "input"))
      (node (ref "U1") (pin "71") (pinfunction "VSS_71") (pintype "input"))
      (node (ref "U1") (pin "73") (pinfunction "VSS_73") (pintype "input"))
      (node (ref "U1") (pin "80") (pinfunction "VSS_80") (pintype "input"))
      (node (ref "U2") (pin "10") (pinfunction "GND_10") (pintype "power_in"))
      (node (ref "U2") (pin "11") (pinfunction "GND_11") (pintype "power_in"))
      (node (ref "U2") (pin "22") (pinfunction "GND_22") (pintype "power_in"))
      (node (ref "U2") (pin "23") (pinfunction "GND_23") (pintype "power_in"))
      (node (ref "U2") (pin "35") (pinfunction "GND_35") (pintype "power_in"))
      (node (ref "U2") (pin "36") (pinfunction "GND_36") (pintype "power_in"))
      (node (ref "U2") (pin "4") (pinfunction "AGND_4") (pintype "power_in"))
      (node (ref "U2") (pin "41") (pinfunction "AGND_41") (pintype "power_in"))
      (node (ref "U2") (pin "42") (pinfunction "TEST_42") (pintype "input"))
      (node (ref "U2") (pin "47") (pinfunction "GND_47") (pintype "power_in"))
      (node (ref "U2") (pin "48") (pinfunction "GND_48") (pintype "power_in"))
      (node (ref "U2") (pin "49") (pinfunction "EP_49") (pintype "passive"))
      (node (ref "U2") (pin "9") (pinfunction "AGND_9") (pintype "power_in"))
      (node (ref "U3") (pin "2") (pinfunction "VSS_2") (pintype "power_in"))
      (node (ref "U4") (pin "12") (pinfunction "GND_12") (pintype "power_in"))
      (node (ref "U5") (pin "11") (pinfunction "GND_11") (pintype "passive"))
      (node (ref "U6") (pin "11") (pinfunction "GND_11") (pintype "passive"))
      (node (ref "U7") (pin "A1") (pinfunction "GND_A1") (pintype "power_in"))
      (node (ref "X1") (pin "4") (pinfunction "4_4") (pintype "passive"))
      (node (ref "X1") (pin "5") (pinfunction "MNT_1_5") (pintype "passive"))
      (node (ref "X1") (pin "6") (pinfunction "MNT_2_6") (pintype "passive"))
      (node (ref "X10") (pin "2") (pinfunction "GND_2") (pintype "passive"))
      (node (ref "X10") (pin "4") (pinfunction "GND_4") (pintype "passive"))
      (node (ref "X11") (pin "3") (pinfunction "3_3") (pintype "passive"))
      (node (ref "X11") (pin "5") (pinfunction "5_5") (pintype "passive"))
      (node (ref "X11") (pin "9") (pinfunction "9_9") (pintype "passive"))
      (node (ref "X12") (pin "3") (pinfunction "3_3") (pintype "passive"))
      (node (ref "X12") (pin "5") (pinfunction "5_5") (pintype "passive"))
      (node (ref "X12") (pin "9") (pinfunction "9_9") (pintype "passive"))
      (node (ref "X13") (pin "3") (pinfunction "3_3") (pintype "passive"))
      (node (ref "X13") (pin "5") (pinfunction "5_5") (pintype "passive"))
      (node (ref "X13") (pin "9") (pinfunction "9_9") (pintype "passive"))
      (node (ref "X14") (pin "3") (pinfunction "3_3") (pintype "passive"))
      (node (ref "X14") (pin "5") (pinfunction "5_5") (pintype "passive"))
      (node (ref "X14") (pin "9") (pinfunction "9_9") (pintype "passive"))
      (node (ref "X15") (pin "3") (pinfunction "3_3") (pintype "passive"))
      (node (ref "X15") (pin "5") (pinfunction "5_5") (pintype "passive"))
      (node (ref "X15") (pin "9") (pinfunction "9_9") (pintype "passive"))
      (node (ref "X16") (pin "3") (pinfunction "3_3") (pintype "passive"))
      (node (ref "X16") (pin "5") (pinfunction "5_5") (pintype "passive"))
      (node (ref "X16") (pin "9") (pinfunction "9_9") (pintype "passive"))
      (node (ref "X17") (pin "3") (pinfunction "3_3") (pintype "passive"))
      (node (ref "X17") (pin "5") (pinfunction "5_5") (pintype "passive"))
      (node (ref "X17") (pin "9") (pinfunction "9_9") (pintype "passive"))
      (node (ref "X2") (pin "4") (pinfunction "4_4") (pintype "passive"))
      (node (ref "X2") (pin "5") (pinfunction "MNT_1_5") (pintype "passive"))
      (node (ref "X2") (pin "6") (pinfunction "MNT_2_6") (pintype "passive"))
      (node (ref "X3") (pin "4") (pinfunction "4_4") (pintype "passive"))
      (node (ref "X3") (pin "5") (pinfunction "MNT_1_5") (pintype "passive"))
      (node (ref "X3") (pin "6") (pinfunction "MNT_2_6") (pintype "passive"))
      (node (ref "X4") (pin "1") (pinfunction "GND_plate/shielding_1") (pintype "power_in"))
      (node (ref "X4") (pin "2") (pinfunction "GND_plate/shielding_2") (pintype "power_in"))
      (node (ref "X4") (pin "3") (pinfunction "MNT_1_3") (pintype "passive"))
      (node (ref "X4") (pin "4") (pinfunction "MNT_2_4") (pintype "passive"))
      (node (ref "X4") (pin "5") (pinfunction "MNT_3_5") (pintype "passive"))
      (node (ref "X4") (pin "6") (pinfunction "MNT_4_6") (pintype "passive"))
      (node (ref "X4") (pin "7") (pinfunction "MNT_5_7") (pintype "passive"))
      (node (ref "X4") (pin "8") (pinfunction "MNT_6_8") (pintype "passive"))
      (node (ref "X4") (pin "A1") (pinfunction "GND_A1") (pintype "power_in"))
      (node (ref "X4") (pin "A12") (pinfunction "GND_A12") (pintype "power_in"))
      (node (ref "X4") (pin "B1") (pinfunction "GND_B1") (pintype "power_in"))
      (node (ref "X4") (pin "B12") (pinfunction "GND_B12") (pintype "power_in"))
      (node (ref "X5") (pin "4") (pinfunction "4_4") (pintype "passive"))
      (node (ref "X5") (pin "5") (pinfunction "MNT_1_5") (pintype "passive"))
      (node (ref "X5") (pin "6") (pinfunction "MNT_2_6") (pintype "passive"))
      (node (ref "X6") (pin "4") (pinfunction "4_4") (pintype "passive"))
      (node (ref "X6") (pin "5") (pinfunction "MNT_1_5") (pintype "passive"))
      (node (ref "X6") (pin "6") (pinfunction "MNT_2_6") (pintype "passive"))
      (node (ref "X7") (pin "4") (pinfunction "4_4") (pintype "passive"))
      (node (ref "X7") (pin "5") (pinfunction "MNT_1_5") (pintype "passive"))
      (node (ref "X7") (pin "6") (pinfunction "MNT_2_6") (pintype "passive"))
      (node (ref "X8") (pin "1") (pinfunction "GND_plate/shielding_1") (pintype "power_in"))
      (node (ref "X8") (pin "2") (pinfunction "GND_plate/shielding_2") (pintype "power_in"))
      (node (ref "X8") (pin "3") (pinfunction "MNT_1_3") (pintype "passive"))
      (node (ref "X8") (pin "4") (pinfunction "MNT_2_4") (pintype "passive"))
      (node (ref "X8") (pin "5") (pinfunction "MNT_3_5") (pintype "passive"))
      (node (ref "X8") (pin "6") (pinfunction "MNT_4_6") (pintype "passive"))
      (node (ref "X8") (pin "7") (pinfunction "MNT_5_7") (pintype "passive"))
      (node (ref "X8") (pin "8") (pinfunction "MNT_6_8") (pintype "passive"))
      (node (ref "X8") (pin "A1") (pinfunction "GND_A1") (pintype "power_in"))
      (node (ref "X8") (pin "A12") (pinfunction "GND_A12") (pintype "power_in"))
      (node (ref "X8") (pin "B1") (pinfunction "GND_B1") (pintype "power_in"))
      (node (ref "X8") (pin "B12") (pinfunction "GND_B12") (pintype "power_in"))
      (node (ref "X9") (pin "2") (pinfunction "GND_2") (pintype "passive"))
      (node (ref "X9") (pin "4") (pinfunction "GND_4") (pintype "passive"))
    )
    (net (code "60") (name "Net-(C16-Pad2)") (class "Default")
      (node (ref "C16") (pin "2") (pinfunction "2_2") (pintype "passive"))
      (node (ref "U1") (pin "33") (pinfunction "VDD18_33") (pintype "input"))
      (node (ref "U1") (pin "50") (pinfunction "VDD18_50") (pintype "input"))
      (node (ref "U1") (pin "72") (pinfunction "VDD18_72") (pintype "input"))
    )
    (net (code "61") (name "Net-(D1-C)") (class "Default")
      (node (ref "D1") (pin "1") (pinfunction "C_1") (pintype "passive"))
      (node (ref "U2") (pin "20") (pinfunction "ADBUS7_20") (pintype "input"))
    )
    (net (code "62") (name "Net-(D2-C)") (class "Default")
      (node (ref "D2") (pin "1") (pinfunction "C_1") (pintype "passive"))
      (node (ref "X17") (pin "10") (pinfunction "10_10") (pintype "passive"))
    )
    (net (code "63") (name "Net-(Q4-D)") (class "Default")
      (node (ref "Q4") (pin "3") (pinfunction "D_3") (pintype "passive"))
      (node (ref "R37") (pin "1") (pinfunction "1_1") (pintype "passive"))
      (node (ref "U6") (pin "13") (pinfunction "/OE_13") (pintype "passive"))
    )
    (net (code "64") (name "Net-(R31-Pad1)") (class "Default")
      (node (ref "R31") (pin "1") (pinfunction "1_1") (pintype "passive"))
      (node (ref "X11") (pin "1") (pinfunction "1_1") (pintype "passive"))
    )
    (net (code "65") (name "Net-(R32-Pad1)") (class "Default")
      (node (ref "R32") (pin "1") (pinfunction "1_1") (pintype "passive"))
      (node (ref "X12") (pin "1") (pinfunction "1_1") (pintype "passive"))
    )
    (net (code "66") (name "Net-(R33-Pad1)") (class "Default")
      (node (ref "R33") (pin "1") (pinfunction "1_1") (pintype "passive"))
      (node (ref "X13") (pin "1") (pinfunction "1_1") (pintype "passive"))
    )
    (net (code "67") (name "Net-(R34-Pad1)") (class "Default")
      (node (ref "R34") (pin "1") (pinfunction "1_1") (pintype "passive"))
      (node (ref "X14") (pin "1") (pinfunction "1_1") (pintype "passive"))
    )
    (net (code "68") (name "Net-(R35-Pad1)") (class "Default")
      (node (ref "R35") (pin "1") (pinfunction "1_1") (pintype "passive"))
      (node (ref "X15") (pin "1") (pinfunction "1_1") (pintype "passive"))
    )
    (net (code "69") (name "Net-(R36-Pad1)") (class "Default")
      (node (ref "R36") (pin "1") (pinfunction "1_1") (pintype "passive"))
      (node (ref "X16") (pin "1") (pinfunction "1_1") (pintype "passive"))
    )
    (net (code "70") (name "Net-(S-COM1)") (class "Default")
      (node (ref "R38") (pin "1") (pinfunction "1_1") (pintype "passive"))
      (node (ref "S") (pin "1A") (pinfunction "COM1_1A") (pintype "passive"))
      (node (ref "U2") (pin "30") (pinfunction "ACBUS6_30") (pintype "bidirectional"))
    )
    (net (code "71") (name "Net-(S-COM2)") (class "Default")
      (node (ref "R27") (pin "1") (pinfunction "1_1") (pintype "passive"))
      (node (ref "S") (pin "2A") (pinfunction "COM2_2A") (pintype "passive"))
      (node (ref "U2") (pin "31") (pinfunction "ACBUS7_31") (pintype "bidirectional"))
    )
    (net (code "72") (name "Net-(U1-AM1{slash}GANG_EN)") (class "Default")
      (node (ref "R5") (pin "2") (pinfunction "2_2") (pintype "passive"))
      (node (ref "U1") (pin "23") (pinfunction "AM1/GANG_EN_23") (pintype "input"))
    )
    (net (code "73") (name "Net-(U1-AM2{slash}MTT_EN)") (class "Default")
      (node (ref "R9") (pin "2") (pinfunction "2_2") (pintype "passive"))
      (node (ref "U1") (pin "25") (pinfunction "AM2/MTT_EN_25") (pintype "input"))
    )
    (net (code "74") (name "Net-(U1-AM4{slash}LED_EN)") (class "Default")
      (node (ref "R12") (pin "2") (pinfunction "2_2") (pintype "passive"))
      (node (ref "U1") (pin "29") (pinfunction "AM4/LED_EN_29") (pintype "input"))
    )
    (net (code "75") (name "Net-(U1-CFG_SEL1)") (class "Default")
      (node (ref "R19") (pin "2") (pinfunction "2_2") (pintype "passive"))
      (node (ref "U1") (pin "20") (pinfunction "CFG_SEL1_20") (pintype "input"))
    )
    (net (code "76") (name "Net-(U1-GR1{slash}NON_REM0)") (class "Default")
      (node (ref "R6") (pin "2") (pinfunction "2_2") (pintype "passive"))
      (node (ref "U1") (pin "24") (pinfunction "GR1/NON_REM0_24") (pintype "input"))
    )
    (net (code "77") (name "Net-(U1-GR2{slash}NON_REM1)") (class "Default")
      (node (ref "R10") (pin "2") (pinfunction "2_2") (pintype "passive"))
      (node (ref "U1") (pin "26") (pinfunction "GR2/NON_REM1_26") (pintype "input"))
    )
    (net (code "78") (name "Net-(U1-GR3{slash}PRT_DIS0)") (class "Default")
      (node (ref "R11") (pin "2") (pinfunction "2_2") (pintype "passive"))
      (node (ref "U1") (pin "28") (pinfunction "GR3/PRT_DIS0_28") (pintype "input"))
    )
    (net (code "79") (name "Net-(U1-GR4{slash}PRT_DIS1)") (class "Default")
      (node (ref "R13") (pin "2") (pinfunction "2_2") (pintype "passive"))
      (node (ref "U1") (pin "30") (pinfunction "GR4/PRT_DIS1_30") (pintype "input"))
    )
    (net (code "80") (name "Net-(U1-RBIAS)") (class "Default")
      (node (ref "R23") (pin "1") (pinfunction "1_1") (pintype "passive"))
      (node (ref "U1") (pin "79") (pinfunction "RBIAS_79") (pintype "input"))
    )
    (net (code "81") (name "Net-(U1-RESET_N)") (class "Default")
      (node (ref "C6") (pin "2") (pinfunction "2_2") (pintype "passive"))
      (node (ref "R15") (pin "2") (pinfunction "2_2") (pintype "passive"))
      (node (ref "U1") (pin "59") (pinfunction "RESET_N_59") (pintype "input"))
    )
    (net (code "82") (name "Net-(U1-SCL{slash}SMBSLK{slash}CFG_SEL0)") (class "Default")
      (node (ref "R2") (pin "1") (pinfunction "1_1") (pintype "passive"))
      (node (ref "R4") (pin "1") (pinfunction "1_1") (pintype "passive"))
      (node (ref "U1") (pin "21") (pinfunction "SCL/SMBSLK/CFG_SEL0_21") (pintype "input"))
    )
    (net (code "83") (name "Net-(U1-SELF_PWR)") (class "Default")
      (node (ref "R17") (pin "2") (pinfunction "2_2") (pintype "passive"))
      (node (ref "R20") (pin "2") (pinfunction "2_2") (pintype "passive"))
      (node (ref "U1") (pin "19") (pinfunction "SELF_PWR_19") (pintype "input"))
    )
    (net (code "84") (name "Net-(U1-VBUS_DET)") (class "Default")
      (node (ref "R1") (pin "1") (pinfunction "1_1") (pintype "passive"))
      (node (ref "R3") (pin "1") (pinfunction "1_1") (pintype "passive"))
      (node (ref "U1") (pin "60") (pinfunction "VBUS_DET_60") (pintype "input"))
    )
    (net (code "85") (name "Net-(U1-VDDA18PLL)") (class "Default")
      (node (ref "C19") (pin "2") (pinfunction "2_2") (pintype "passive"))
      (node (ref "U1") (pin "76") (pinfunction "VDDA18PLL_76") (pintype "input"))
    )
    (net (code "86") (name "Net-(U1-XTAL1{slash}CLKIN)") (class "Default")
      (node (ref "U1") (pin "75") (pinfunction "XTAL1/CLKIN_75") (pintype "input"))
      (node (ref "X9") (pin "3") (pinfunction "Crystal_3") (pintype "passive"))
    )
    (net (code "87") (name "Net-(U1-XTAL2)") (class "Default")
      (node (ref "U1") (pin "74") (pinfunction "XTAL2_74") (pintype "input"))
      (node (ref "X9") (pin "1") (pinfunction "Crystal_1") (pintype "passive"))
    )
    (net (code "88") (name "Net-(U2-EECLK)") (class "Default")
      (node (ref "U2") (pin "44") (pinfunction "EECLK_44") (pintype "output"))
      (node (ref "U3") (pin "4") (pinfunction "CLK_4") (pintype "input"))
    )
    (net (code "89") (name "Net-(U2-EECS)") (class "Default")
      (node (ref "U2") (pin "45") (pinfunction "EECS_45") (pintype "bidirectional"))
      (node (ref "U3") (pin "5") (pinfunction "CS_5") (pintype "input"))
    )
    (net (code "90") (name "Net-(U2-EEDATA)") (class "Default")
      (node (ref "R29") (pin "2") (pinfunction "2_2") (pintype "passive"))
      (node (ref "U2") (pin "43") (pinfunction "EEDATA_43") (pintype "bidirectional"))
      (node (ref "U3") (pin "3") (pinfunction "DI_3") (pintype "input"))
    )
    (net (code "91") (name "Net-(U2-OSCI)") (class "Default")
      (node (ref "C20") (pin "1") (pinfunction "1_1") (pintype "passive"))
      (node (ref "U2") (pin "1") (pinfunction "OSCI_1") (pintype "input"))
      (node (ref "X10") (pin "1") (pinfunction "Crystal_1") (pintype "passive"))
    )
    (net (code "92") (name "Net-(U2-OSCO)") (class "Default")
      (node (ref "C21") (pin "1") (pinfunction "1_1") (pintype "passive"))
      (node (ref "U2") (pin "2") (pinfunction "OSCO_2") (pintype "output"))
      (node (ref "X10") (pin "3") (pinfunction "Crystal_3") (pintype "passive"))
    )
    (net (code "93") (name "Net-(U2-REF)") (class "Default")
      (node (ref "R25") (pin "2") (pinfunction "2_2") (pintype "passive"))
      (node (ref "U2") (pin "5") (pinfunction "REF_5") (pintype "passive"))
    )
    (net (code "94") (name "Net-(U2-VCCA)") (class "Default")
      (node (ref "C4") (pin "2") (pinfunction "2_2") (pintype "passive"))
      (node (ref "U2") (pin "37") (pinfunction "VCCA_37") (pintype "power_in"))
    )
    (net (code "95") (name "Net-(U2-VCCCORE)") (class "Default")
      (node (ref "C2") (pin "2") (pinfunction "2_2") (pintype "passive"))
      (node (ref "U2") (pin "38") (pinfunction "VCCCORE_38") (pintype "power_in"))
    )
    (net (code "96") (name "Net-(U2-~{RESET})") (class "Default")
      (node (ref "C32") (pin "2") (pinfunction "2_2") (pintype "passive"))
      (node (ref "R30") (pin "2") (pinfunction "2_2") (pintype "passive"))
      (node (ref "U2") (pin "34") (pinfunction "~{RESET}_34") (pintype "input"))
    )
    (net (code "97") (name "Net-(U3-DO)") (class "Default")
      (node (ref "R29") (pin "1") (pinfunction "1_1") (pintype "passive"))
      (node (ref "U3") (pin "1") (pinfunction "DO_1") (pintype "output"))
    )
    (net (code "98") (name "Net-(U7-EN)") (class "Default")
      (node (ref "C37") (pin "2") (pinfunction "2_2") (pintype "passive"))
      (node (ref "R47") (pin "2") (pinfunction "2_2") (pintype "passive"))
      (node (ref "U7") (pin "A2") (pinfunction "EN_A2") (pintype "input"))
      (node (ref "U7") (pin "B2") (pinfunction "VREF2_B2") (pintype "power_in"))
    )
    (net (code "99") (name "Net-(X4-CC1)") (class "Default")
      (node (ref "R7") (pin "2") (pinfunction "2_2") (pintype "passive"))
      (node (ref "X4") (pin "A5") (pinfunction "CC1_A5") (pintype "passive"))
    )
    (net (code "100") (name "Net-(X4-CC2)") (class "Default")
      (node (ref "R8") (pin "2") (pinfunction "2_2") (pintype "passive"))
      (node (ref "X4") (pin "B5") (pinfunction "CC2_B5") (pintype "passive"))
    )
    (net (code "101") (name "Net-(X8-CC1)") (class "Default")
      (node (ref "R24") (pin "2") (pinfunction "2_2") (pintype "passive"))
      (node (ref "X8") (pin "A5") (pinfunction "CC1_A5") (pintype "passive"))
    )
    (net (code "102") (name "Net-(X8-CC2)") (class "Default")
      (node (ref "R26") (pin "2") (pinfunction "2_2") (pintype "passive"))
      (node (ref "X8") (pin "B5") (pinfunction "CC2_B5") (pintype "passive"))
    )
    (net (code "103") (name "unconnected-(U1-AM3-Pad27)") (class "Default")
      (node (ref "U1") (pin "27") (pinfunction "AM3_27") (pintype "input+no_connect"))
    )
    (net (code "104") (name "unconnected-(U1-AM5-Pad34)") (class "Default")
      (node (ref "U1") (pin "34") (pinfunction "AM5_34") (pintype "input+no_connect"))
    )
    (net (code "105") (name "unconnected-(U1-AM6-Pad36)") (class "Default")
      (node (ref "U1") (pin "36") (pinfunction "AM6_36") (pintype "input+no_connect"))
    )
    (net (code "106") (name "unconnected-(U1-AM7-Pad38)") (class "Default")
      (node (ref "U1") (pin "38") (pinfunction "AM7_38") (pintype "input+no_connect"))
    )
    (net (code "107") (name "unconnected-(U1-GR5-Pad35)") (class "Default")
      (node (ref "U1") (pin "35") (pinfunction "GR5_35") (pintype "input+no_connect"))
    )
    (net (code "108") (name "unconnected-(U1-GR6-Pad37)") (class "Default")
      (node (ref "U1") (pin "37") (pinfunction "GR6_37") (pintype "input+no_connect"))
    )
    (net (code "109") (name "unconnected-(U1-GR7-Pad39)") (class "Default")
      (node (ref "U1") (pin "39") (pinfunction "GR7_39") (pintype "input+no_connect"))
    )
    (net (code "110") (name "unconnected-(U1-OCS1_N-Pad41)") (class "Default")
      (node (ref "U1") (pin "41") (pinfunction "OCS1_N_41") (pintype "input+no_connect"))
    )
    (net (code "111") (name "unconnected-(U1-OCS2_N-Pad43)") (class "Default")
      (node (ref "U1") (pin "43") (pinfunction "OCS2_N_43") (pintype "input+no_connect"))
    )
    (net (code "112") (name "unconnected-(U1-OCS3_N-Pad45)") (class "Default")
      (node (ref "U1") (pin "45") (pinfunction "OCS3_N_45") (pintype "input+no_connect"))
    )
    (net (code "113") (name "unconnected-(U1-OCS4_N-Pad47)") (class "Default")
      (node (ref "U1") (pin "47") (pinfunction "OCS4_N_47") (pintype "input+no_connect"))
    )
    (net (code "114") (name "unconnected-(U1-OCS5_N-Pad52)") (class "Default")
      (node (ref "U1") (pin "52") (pinfunction "OCS5_N_52") (pintype "input+no_connect"))
    )
    (net (code "115") (name "unconnected-(U1-OCS6_N-Pad54)") (class "Default")
      (node (ref "U1") (pin "54") (pinfunction "OCS6_N_54") (pintype "input+no_connect"))
    )
    (net (code "116") (name "unconnected-(U1-OCS7_N-Pad56)") (class "Default")
      (node (ref "U1") (pin "56") (pinfunction "OCS7_N_56") (pintype "input+no_connect"))
    )
    (net (code "117") (name "unconnected-(U1-PRTPWR1-Pad40)") (class "Default")
      (node (ref "U1") (pin "40") (pinfunction "PRTPWR1_40") (pintype "input+no_connect"))
    )
    (net (code "118") (name "unconnected-(U1-PRTPWR2-Pad42)") (class "Default")
      (node (ref "U1") (pin "42") (pinfunction "PRTPWR2_42") (pintype "input+no_connect"))
    )
    (net (code "119") (name "unconnected-(U1-PRTPWR3-Pad44)") (class "Default")
      (node (ref "U1") (pin "44") (pinfunction "PRTPWR3_44") (pintype "input+no_connect"))
    )
    (net (code "120") (name "unconnected-(U1-PRTPWR4-Pad46)") (class "Default")
      (node (ref "U1") (pin "46") (pinfunction "PRTPWR4_46") (pintype "input+no_connect"))
    )
    (net (code "121") (name "unconnected-(U1-PRTPWR5-Pad48)") (class "Default")
      (node (ref "U1") (pin "48") (pinfunction "PRTPWR5_48") (pintype "input+no_connect"))
    )
    (net (code "122") (name "unconnected-(U1-PRTPWR6-Pad53)") (class "Default")
      (node (ref "U1") (pin "53") (pinfunction "PRTPWR6_53") (pintype "input+no_connect"))
    )
    (net (code "123") (name "unconnected-(U1-PRTPWR7-Pad55)") (class "Default")
      (node (ref "U1") (pin "55") (pinfunction "PRTPWR7_55") (pintype "input+no_connect"))
    )
    (net (code "124") (name "unconnected-(U1-SDA{slash}SMBDATA-Pad22)") (class "Default")
      (node (ref "U1") (pin "22") (pinfunction "SDA/SMBDATA_22") (pintype "input+no_connect"))
    )
    (net (code "125") (name "unconnected-(U1-TEST0-Pad17)") (class "Default")
      (node (ref "U1") (pin "17") (pinfunction "TEST0_17") (pintype "input+no_connect"))
    )
    (net (code "126") (name "unconnected-(U1-TEST1-Pad18)") (class "Default")
      (node (ref "U1") (pin "18") (pinfunction "TEST1_18") (pintype "input+no_connect"))
    )
    (net (code "127") (name "unconnected-(U2-ACBUS8-Pad32)") (class "Default")
      (node (ref "U2") (pin "32") (pinfunction "ACBUS8_32") (pintype "bidirectional"))
    )
    (net (code "128") (name "unconnected-(U2-ACBUS9-Pad33)") (class "Default")
      (node (ref "U2") (pin "33") (pinfunction "ACBUS9_33") (pintype "bidirectional"))
    )
    (net (code "129") (name "unconnected-(U2-ADBUS0-Pad13)") (class "Default")
      (node (ref "U2") (pin "13") (pinfunction "ADBUS0_13") (pintype "output"))
    )
    (net (code "130") (name "unconnected-(U2-ADBUS1-Pad14)") (class "Default")
      (node (ref "U2") (pin "14") (pinfunction "ADBUS1_14") (pintype "input+no_connect"))
    )
    (net (code "131") (name "unconnected-(U2-ADBUS2-Pad15)") (class "Default")
      (node (ref "U2") (pin "15") (pinfunction "ADBUS2_15") (pintype "output+no_connect"))
    )
    (net (code "132") (name "unconnected-(U2-ADBUS3-Pad16)") (class "Default")
      (node (ref "U2") (pin "16") (pinfunction "ADBUS3_16") (pintype "input+no_connect"))
    )
    (net (code "133") (name "unconnected-(U4-NC-Pad1)") (class "Default")
      (node (ref "U4") (pin "1") (pinfunction "NC_1") (pintype "passive"))
    )
    (net (code "134") (name "unconnected-(U4-S7-Pad8)") (class "Default")
      (node (ref "U4") (pin "8") (pinfunction "S7_8") (pintype "bidirectional"))
    )
    (net (code "135") (name "unconnected-(U4-S8-Pad7)") (class "Default")
      (node (ref "U4") (pin "7") (pinfunction "S8_7") (pintype "bidirectional"))
    )
    (net (code "136") (name "unconnected-(U6-1S3-Pad16)") (class "Default")
      (node (ref "U6") (pin "16") (pinfunction "1S3_16") (pintype "passive"))
    )
    (net (code "137") (name "unconnected-(U6-1S4-Pad1)") (class "Default")
      (node (ref "U6") (pin "1") (pinfunction "1S4_1") (pintype "passive"))
    )
    (net (code "138") (name "unconnected-(U6-2S3-Pad8)") (class "Default")
      (node (ref "U6") (pin "8") (pinfunction "2S3_8") (pintype "passive"))
    )
    (net (code "139") (name "unconnected-(U6-2S4-Pad9)") (class "Default")
      (node (ref "U6") (pin "9") (pinfunction "2S4_9") (pintype "passive"))
    )
    (net (code "140") (name "unconnected-(X4-SBU1-PadA8)") (class "Default")
      (node (ref "X4") (pin "A8") (pinfunction "SBU1_A8") (pintype "passive+no_connect"))
    )
    (net (code "141") (name "unconnected-(X4-SBU2-PadB8)") (class "Default")
      (node (ref "X4") (pin "B8") (pinfunction "SBU2_B8") (pintype "passive+no_connect"))
    )
    (net (code "142") (name "unconnected-(X4-SSRXn1-PadB10)") (class "Default")
      (node (ref "X4") (pin "B10") (pinfunction "SSRXn1_B10") (pintype "input+no_connect"))
    )
    (net (code "143") (name "unconnected-(X4-SSRXn2-PadA10)") (class "Default")
      (node (ref "X4") (pin "A10") (pinfunction "SSRXn2_A10") (pintype "input+no_connect"))
    )
    (net (code "144") (name "unconnected-(X4-SSRXp1-PadB11)") (class "Default")
      (node (ref "X4") (pin "B11") (pinfunction "SSRXp1_B11") (pintype "input+no_connect"))
    )
    (net (code "145") (name "unconnected-(X4-SSRXp2-PadA11)") (class "Default")
      (node (ref "X4") (pin "A11") (pinfunction "SSRXp2_A11") (pintype "input+no_connect"))
    )
    (net (code "146") (name "unconnected-(X4-SSTXn1-PadA3)") (class "Default")
      (node (ref "X4") (pin "A3") (pinfunction "SSTXn1_A3") (pintype "output+no_connect"))
    )
    (net (code "147") (name "unconnected-(X4-SSTXn2-PadB3)") (class "Default")
      (node (ref "X4") (pin "B3") (pinfunction "SSTXn2_B3") (pintype "output+no_connect"))
    )
    (net (code "148") (name "unconnected-(X4-SSTXp1-PadA2)") (class "Default")
      (node (ref "X4") (pin "A2") (pinfunction "SSTXp1_A2") (pintype "output+no_connect"))
    )
    (net (code "149") (name "unconnected-(X4-SSTXp2-PadB2)") (class "Default")
      (node (ref "X4") (pin "B2") (pinfunction "SSTXp2_B2") (pintype "output+no_connect"))
    )
    (net (code "150") (name "unconnected-(X8-Dn1-PadA7)") (class "Default")
      (node (ref "X8") (pin "A7") (pinfunction "Dn1_A7") (pintype "bidirectional"))
    )
    (net (code "151") (name "unconnected-(X8-Dn2-PadB7)") (class "Default")
      (node (ref "X8") (pin "B7") (pinfunction "Dn2_B7") (pintype "bidirectional"))
    )
    (net (code "152") (name "unconnected-(X8-Dp1-PadA6)") (class "Default")
      (node (ref "X8") (pin "A6") (pinfunction "Dp1_A6") (pintype "bidirectional"))
    )
    (net (code "153") (name "unconnected-(X8-Dp2-PadB6)") (class "Default")
      (node (ref "X8") (pin "B6") (pinfunction "Dp2_B6") (pintype "bidirectional"))
    )
    (net (code "154") (name "unconnected-(X8-SBU1-PadA8)") (class "Default")
      (node (ref "X8") (pin "A8") (pinfunction "SBU1_A8") (pintype "passive"))
    )
    (net (code "155") (name "unconnected-(X8-SBU2-PadB8)") (class "Default")
      (node (ref "X8") (pin "B8") (pinfunction "SBU2_B8") (pintype "passive"))
    )
    (net (code "156") (name "unconnected-(X8-SSRXn1-PadB10)") (class "Default")
      (node (ref "X8") (pin "B10") (pinfunction "SSRXn1_B10") (pintype "input+no_connect"))
    )
    (net (code "157") (name "unconnected-(X8-SSRXn2-PadA10)") (class "Default")
      (node (ref "X8") (pin "A10") (pinfunction "SSRXn2_A10") (pintype "input+no_connect"))
    )
    (net (code "158") (name "unconnected-(X8-SSRXp1-PadB11)") (class "Default")
      (node (ref "X8") (pin "B11") (pinfunction "SSRXp1_B11") (pintype "input+no_connect"))
    )
    (net (code "159") (name "unconnected-(X8-SSRXp2-PadA11)") (class "Default")
      (node (ref "X8") (pin "A11") (pinfunction "SSRXp2_A11") (pintype "input+no_connect"))
    )
    (net (code "160") (name "unconnected-(X8-SSTXn1-PadA3)") (class "Default")
      (node (ref "X8") (pin "A3") (pinfunction "SSTXn1_A3") (pintype "output"))
    )
    (net (code "161") (name "unconnected-(X8-SSTXn2-PadB3)") (class "Default")
      (node (ref "X8") (pin "B3") (pinfunction "SSTXn2_B3") (pintype "output"))
    )
    (net (code "162") (name "unconnected-(X8-SSTXp1-PadA2)") (class "Default")
      (node (ref "X8") (pin "A2") (pinfunction "SSTXp1_A2") (pintype "output"))
    )
    (net (code "163") (name "unconnected-(X8-SSTXp2-PadB2)") (class "Default")
      (node (ref "X8") (pin "B2") (pinfunction "SSTXp2_B2") (pintype "output"))
    )
    (net (code "164") (name "unconnected-(X11-Pad6)") (class "Default")
      (node (ref "X11") (pin "6") (pinfunction "6_6") (pintype "passive"))
    )
    (net (code "165") (name "unconnected-(X11-Pad7)") (class "Default")
      (node (ref "X11") (pin "7") (pinfunction "7_7") (pintype "passive"))
    )
    (net (code "166") (name "unconnected-(X11-Pad8)") (class "Default")
      (node (ref "X11") (pin "8") (pinfunction "8_8") (pintype "passive"))
    )
    (net (code "167") (name "unconnected-(X12-Pad6)") (class "Default")
      (node (ref "X12") (pin "6") (pinfunction "6_6") (pintype "passive"))
    )
    (net (code "168") (name "unconnected-(X12-Pad7)") (class "Default")
      (node (ref "X12") (pin "7") (pinfunction "7_7") (pintype "passive"))
    )
    (net (code "169") (name "unconnected-(X12-Pad8)") (class "Default")
      (node (ref "X12") (pin "8") (pinfunction "8_8") (pintype "passive"))
    )
    (net (code "170") (name "unconnected-(X13-Pad6)") (class "Default")
      (node (ref "X13") (pin "6") (pinfunction "6_6") (pintype "passive"))
    )
    (net (code "171") (name "unconnected-(X13-Pad7)") (class "Default")
      (node (ref "X13") (pin "7") (pinfunction "7_7") (pintype "passive"))
    )
    (net (code "172") (name "unconnected-(X13-Pad8)") (class "Default")
      (node (ref "X13") (pin "8") (pinfunction "8_8") (pintype "passive"))
    )
    (net (code "173") (name "unconnected-(X14-Pad6)") (class "Default")
      (node (ref "X14") (pin "6") (pinfunction "6_6") (pintype "passive"))
    )
    (net (code "174") (name "unconnected-(X14-Pad7)") (class "Default")
      (node (ref "X14") (pin "7") (pinfunction "7_7") (pintype "passive"))
    )
    (net (code "175") (name "unconnected-(X14-Pad8)") (class "Default")
      (node (ref "X14") (pin "8") (pinfunction "8_8") (pintype "passive"))
    )
    (net (code "176") (name "unconnected-(X15-Pad6)") (class "Default")
      (node (ref "X15") (pin "6") (pinfunction "6_6") (pintype "passive"))
    )
    (net (code "177") (name "unconnected-(X15-Pad7)") (class "Default")
      (node (ref "X15") (pin "7") (pinfunction "7_7") (pintype "passive"))
    )
    (net (code "178") (name "unconnected-(X15-Pad8)") (class "Default")
      (node (ref "X15") (pin "8") (pinfunction "8_8") (pintype "passive"))
    )
    (net (code "179") (name "unconnected-(X16-Pad6)") (class "Default")
      (node (ref "X16") (pin "6") (pinfunction "6_6") (pintype "passive"))
    )
    (net (code "180") (name "unconnected-(X16-Pad7)") (class "Default")
      (node (ref "X16") (pin "7") (pinfunction "7_7") (pintype "passive"))
    )
    (net (code "181") (name "unconnected-(X16-Pad8)") (class "Default")
      (node (ref "X16") (pin "8") (pinfunction "8_8") (pintype "passive"))
    )
    (net (code "182") (name "unconnected-(X17-Pad6)") (class "Default")
      (node (ref "X17") (pin "6") (pinfunction "6_6") (pintype "passive"))
    )
    (net (code "183") (name "unconnected-(X17-Pad7)") (class "Default")
      (node (ref "X17") (pin "7") (pinfunction "7_7") (pintype "passive"))
    )
    (net (code "184") (name "unconnected-(X17-Pad8)") (class "Default")
      (node (ref "X17") (pin "8") (pinfunction "8_8") (pintype "passive"))
    )
  )
)
